# canSlaveV01a0.net
KiCad netlist of a schematic drawn in EAGLE
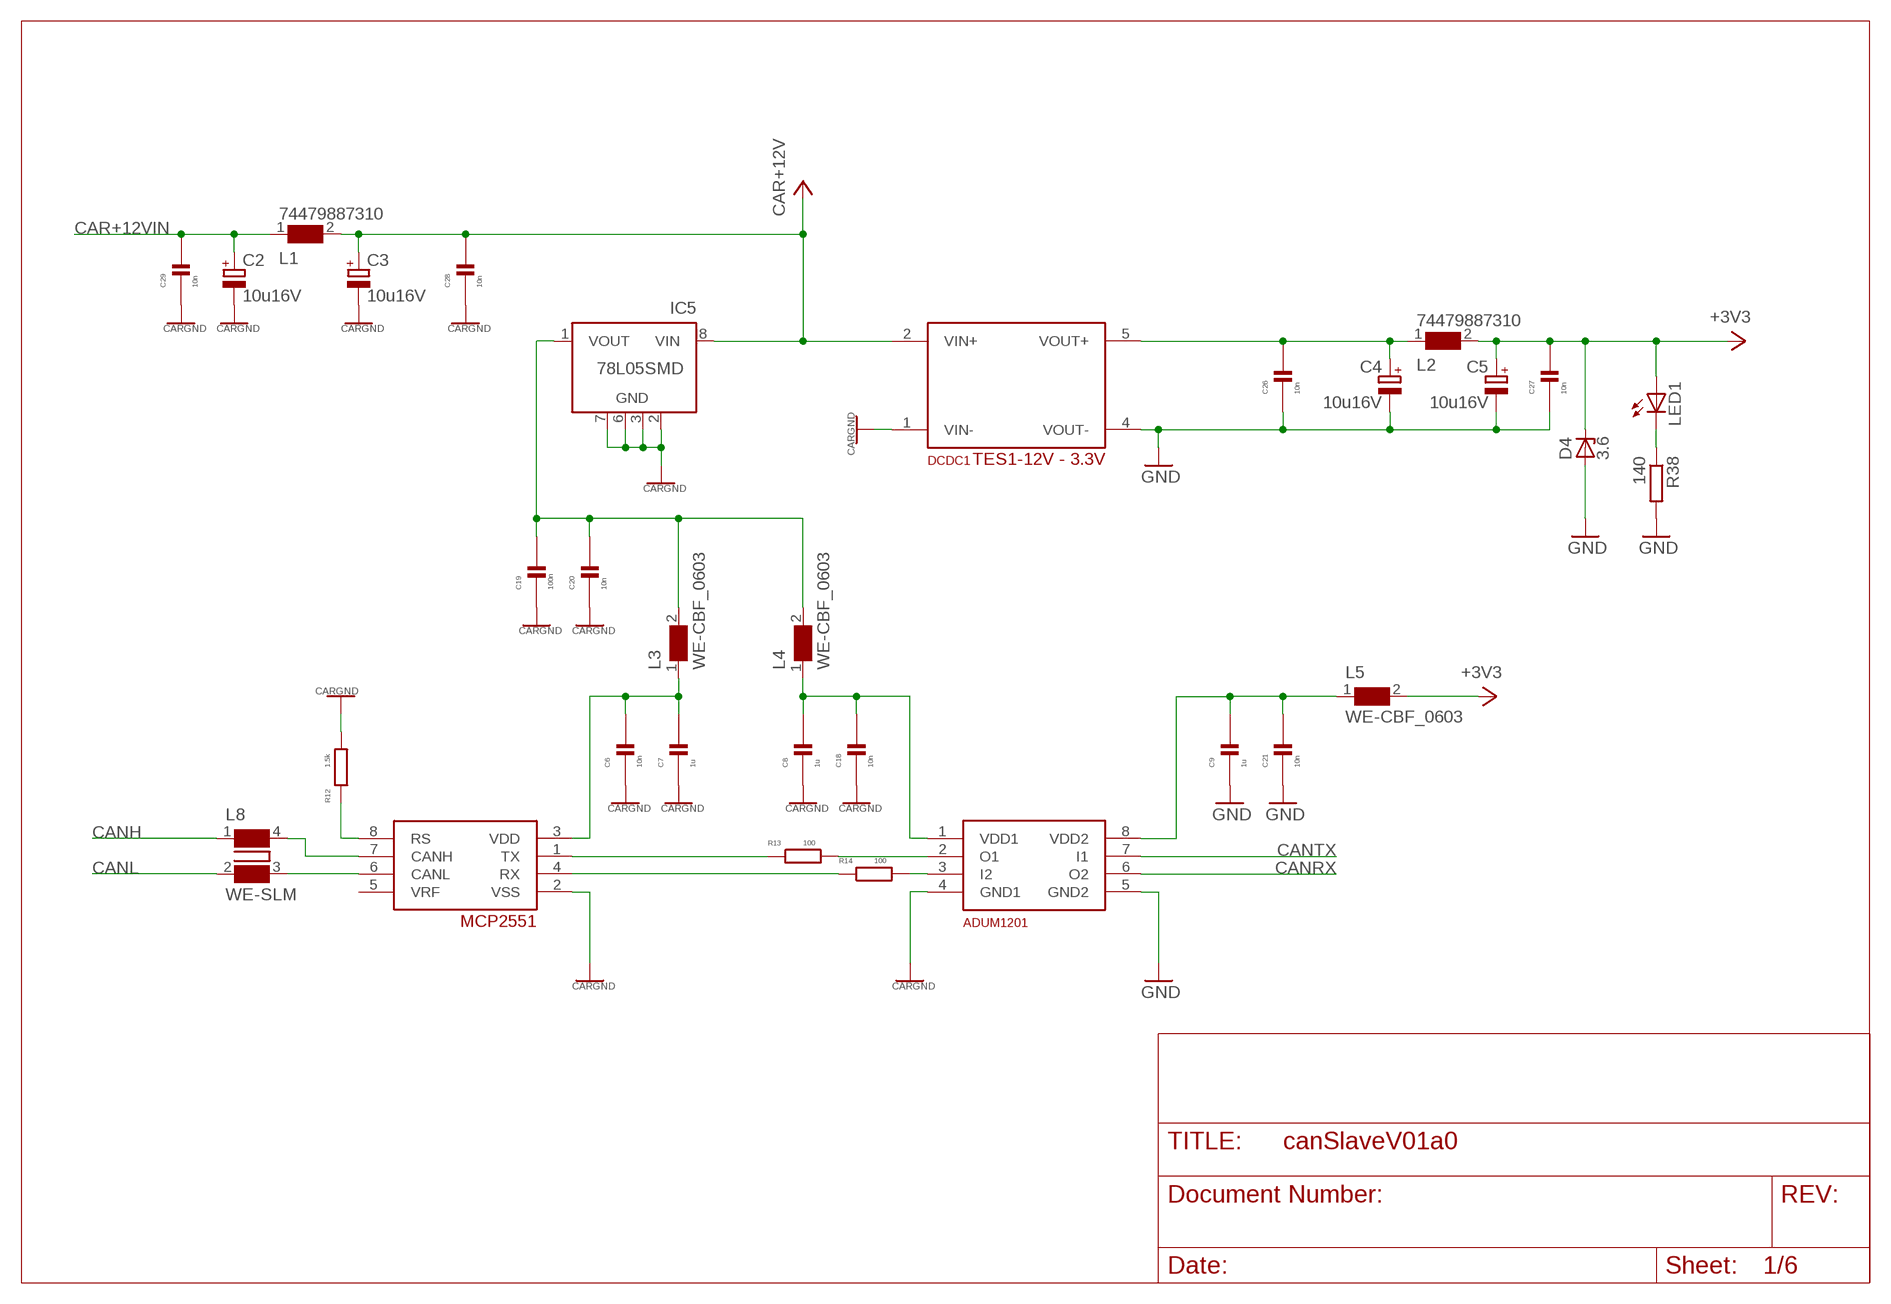
[diagram p0: schematic, sheet 1]
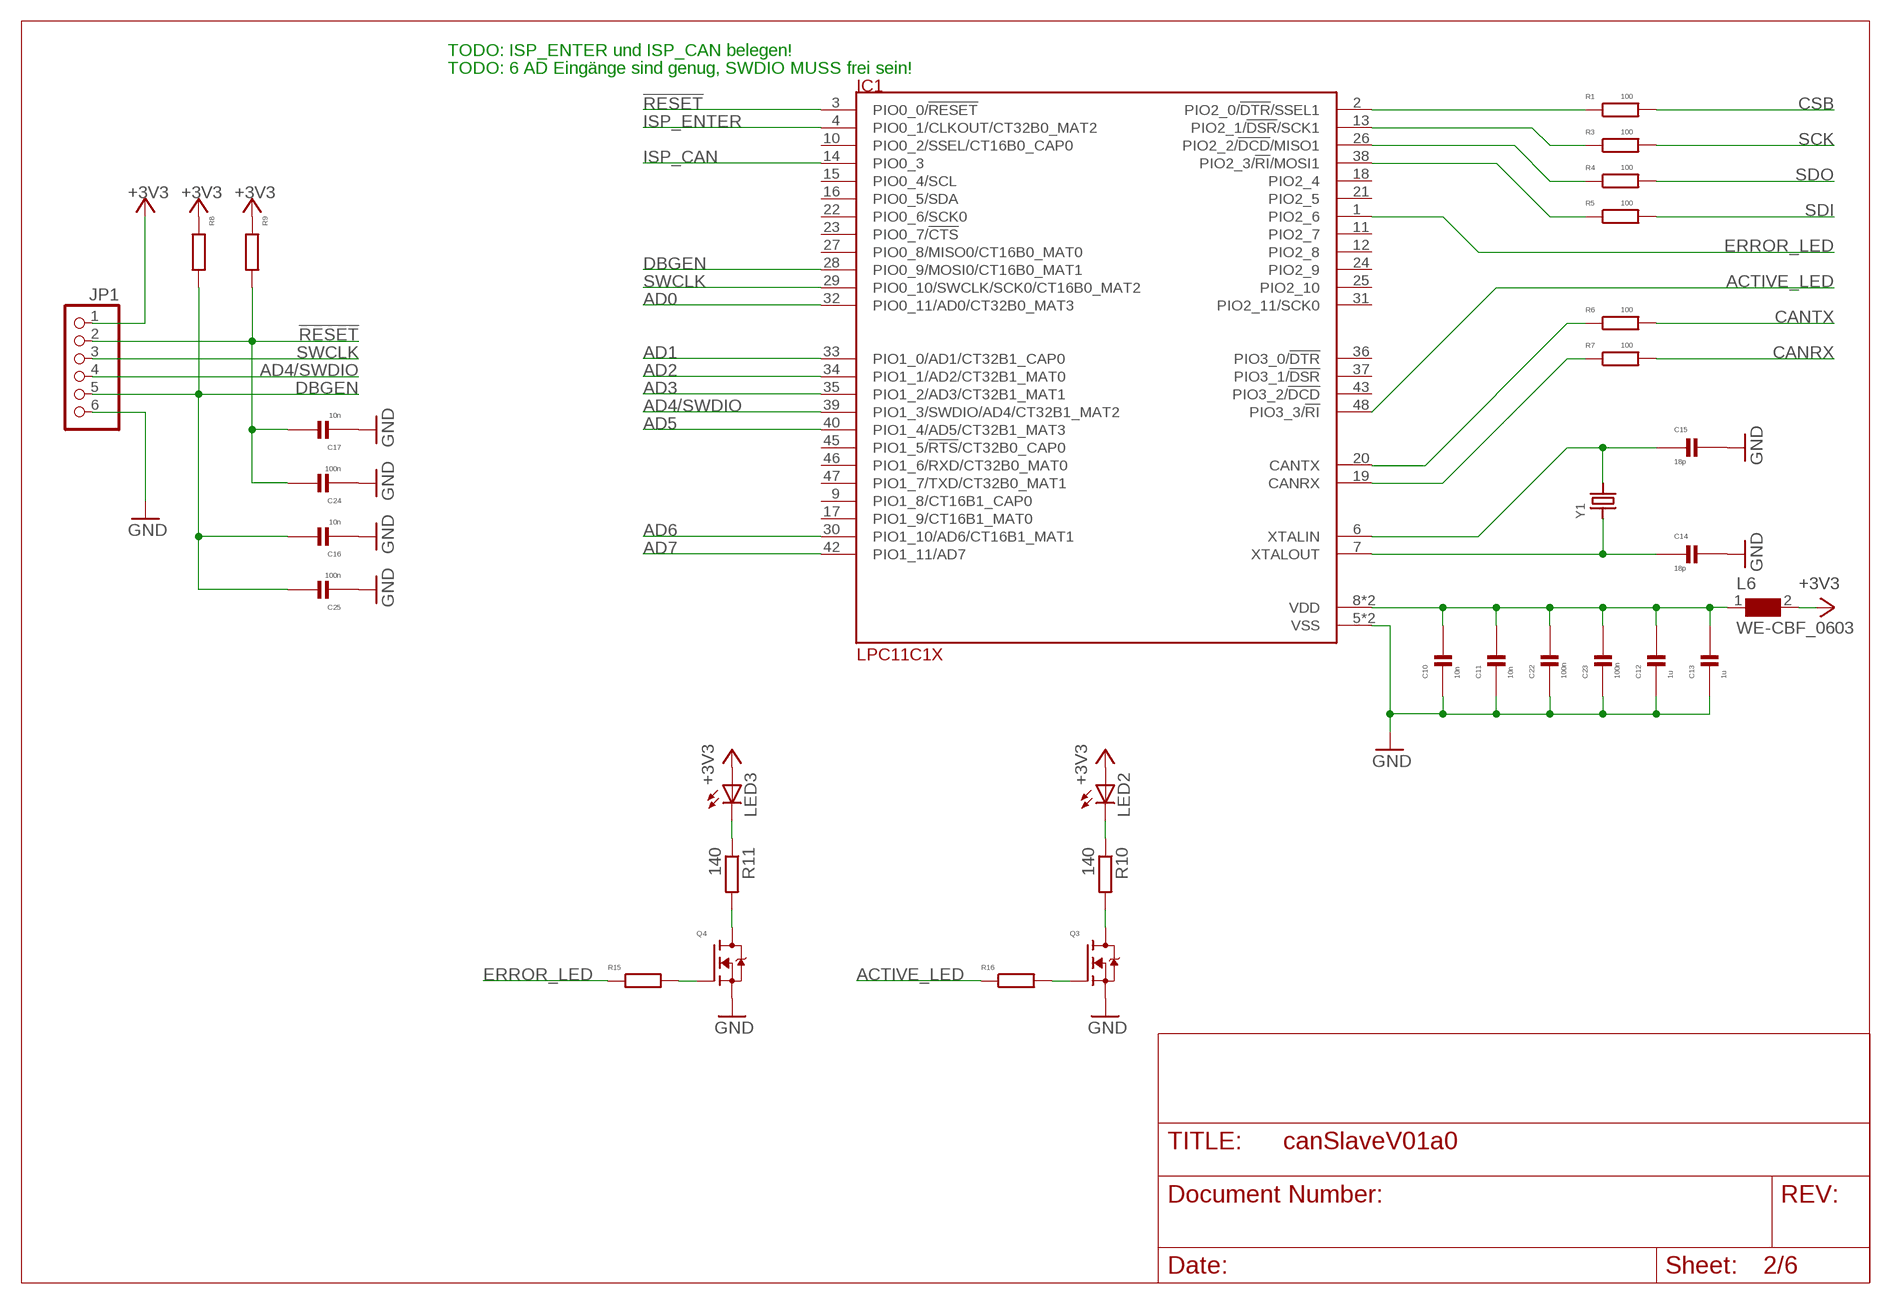
[diagram p1: schematic, sheet 2]
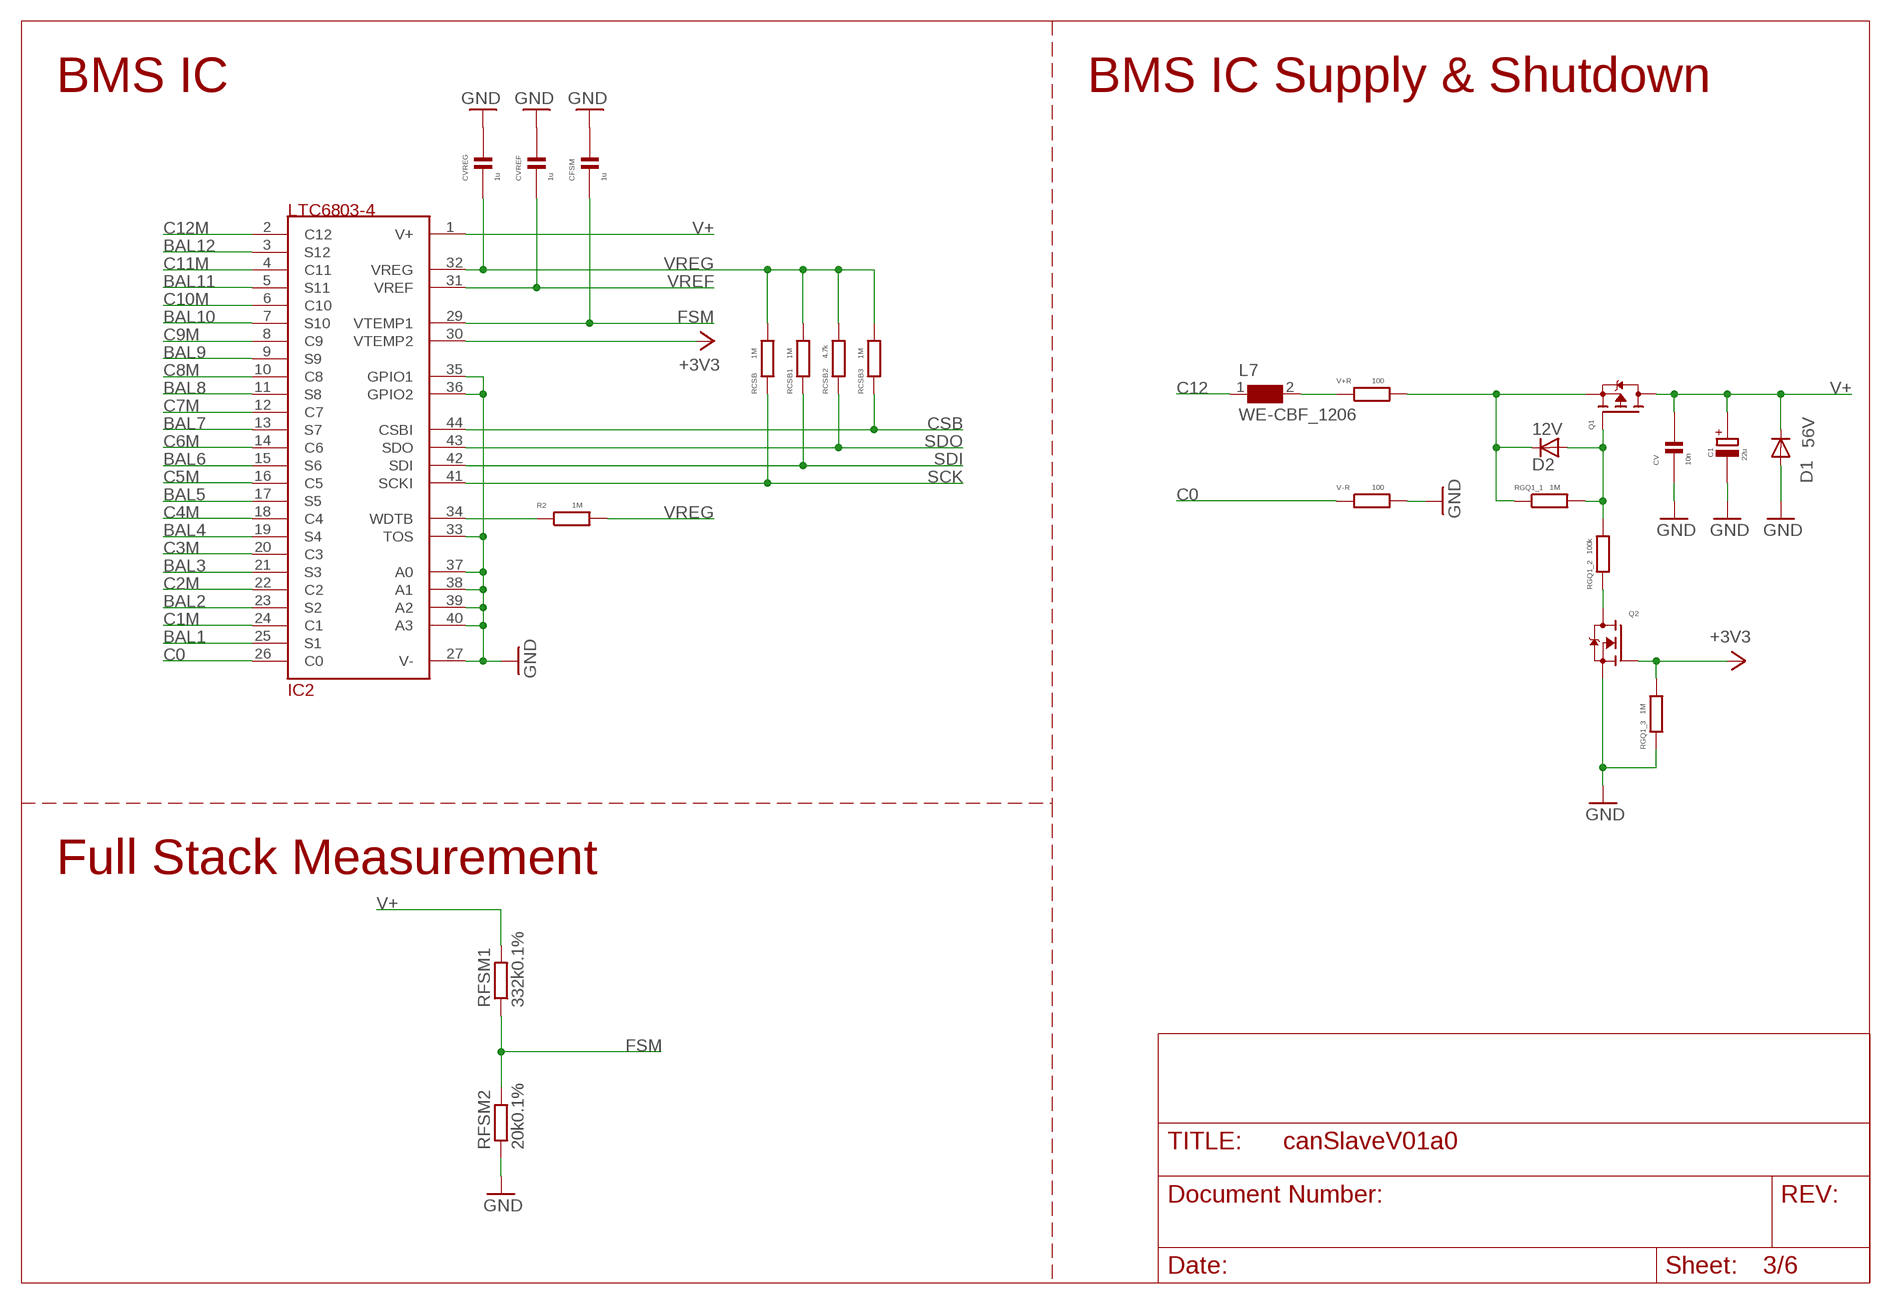
[diagram p2: schematic, sheet 3]
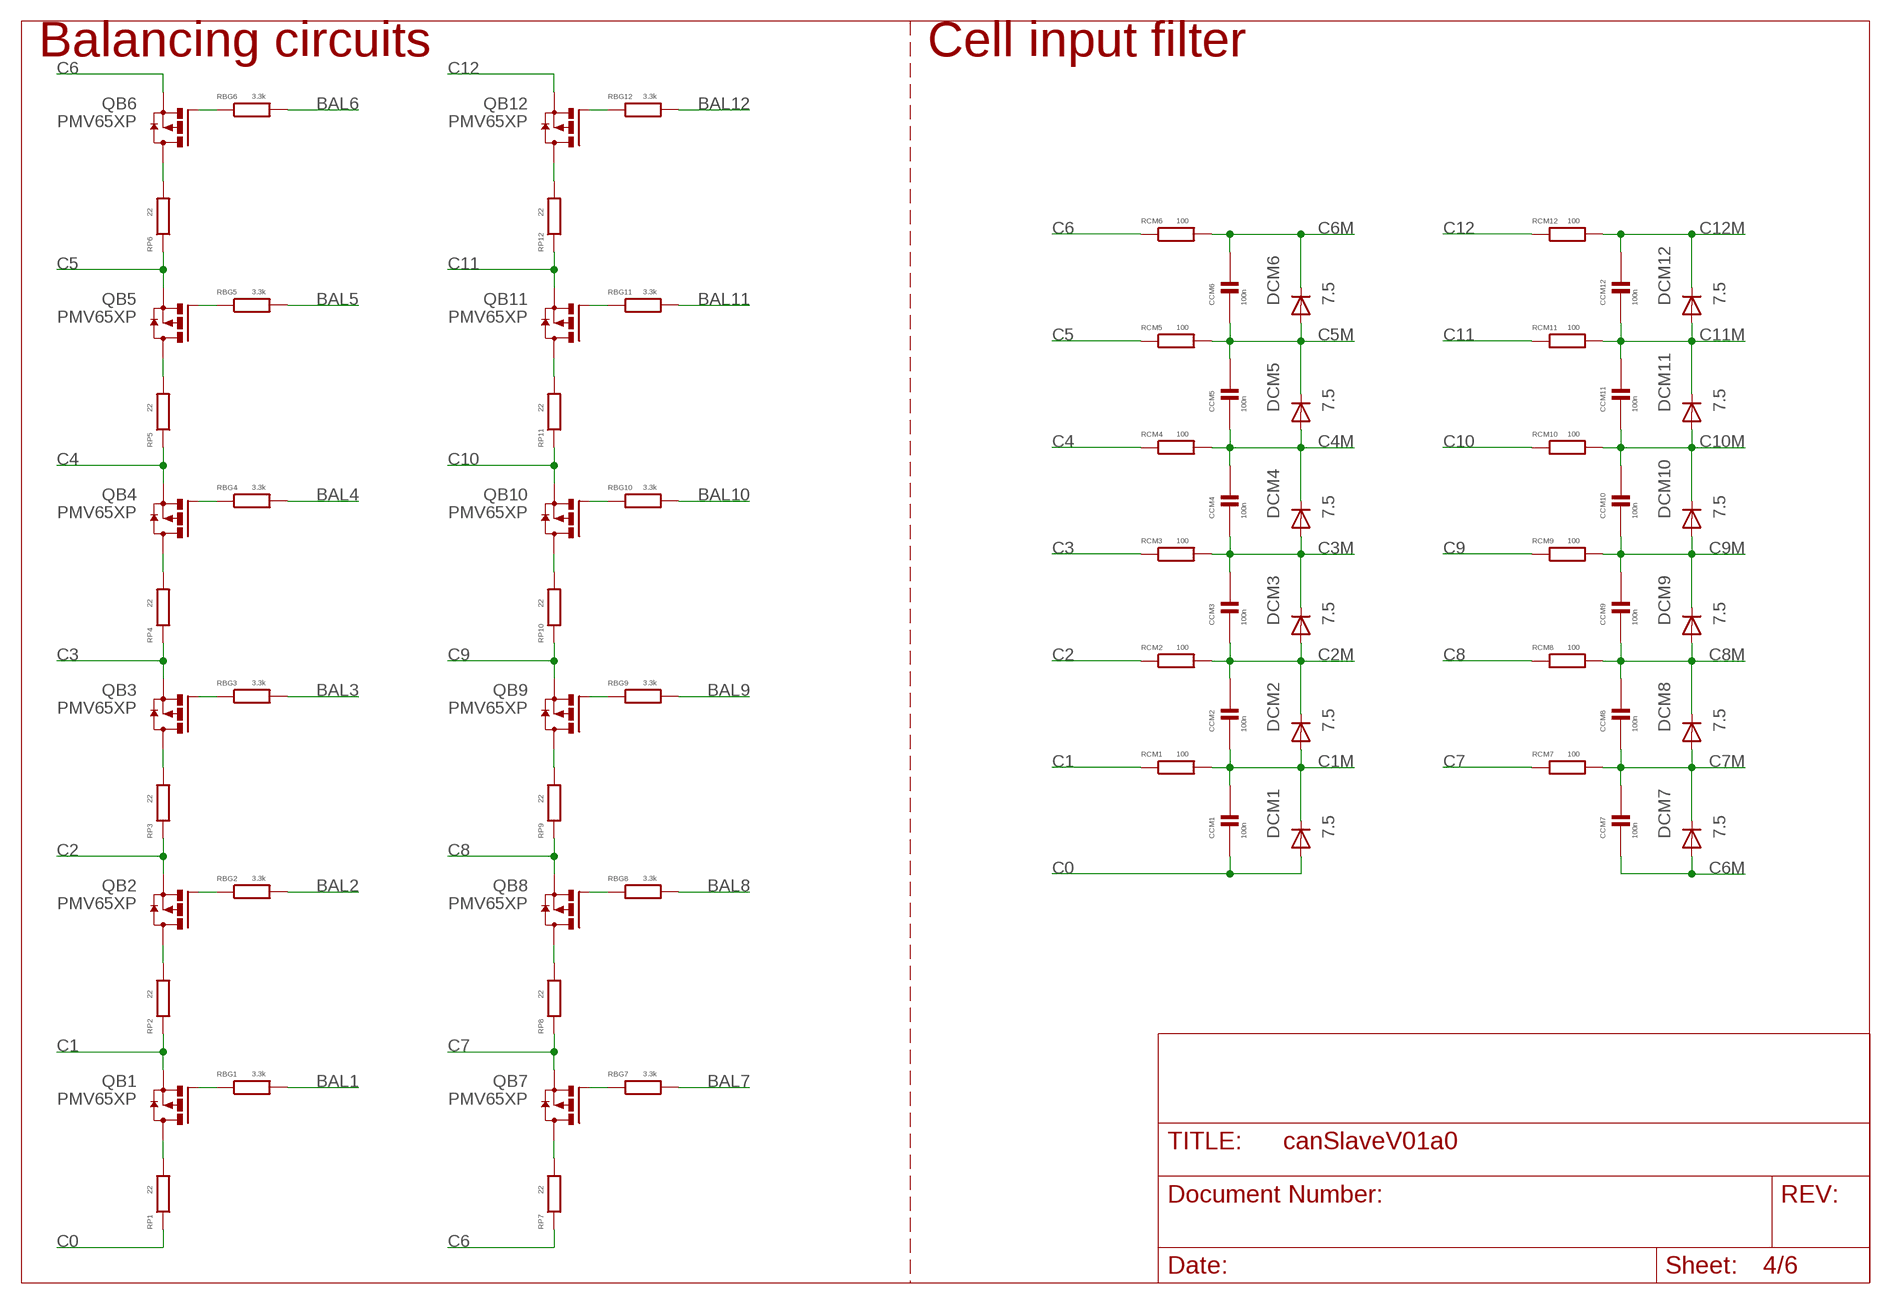
[diagram p3: schematic, sheet 4]
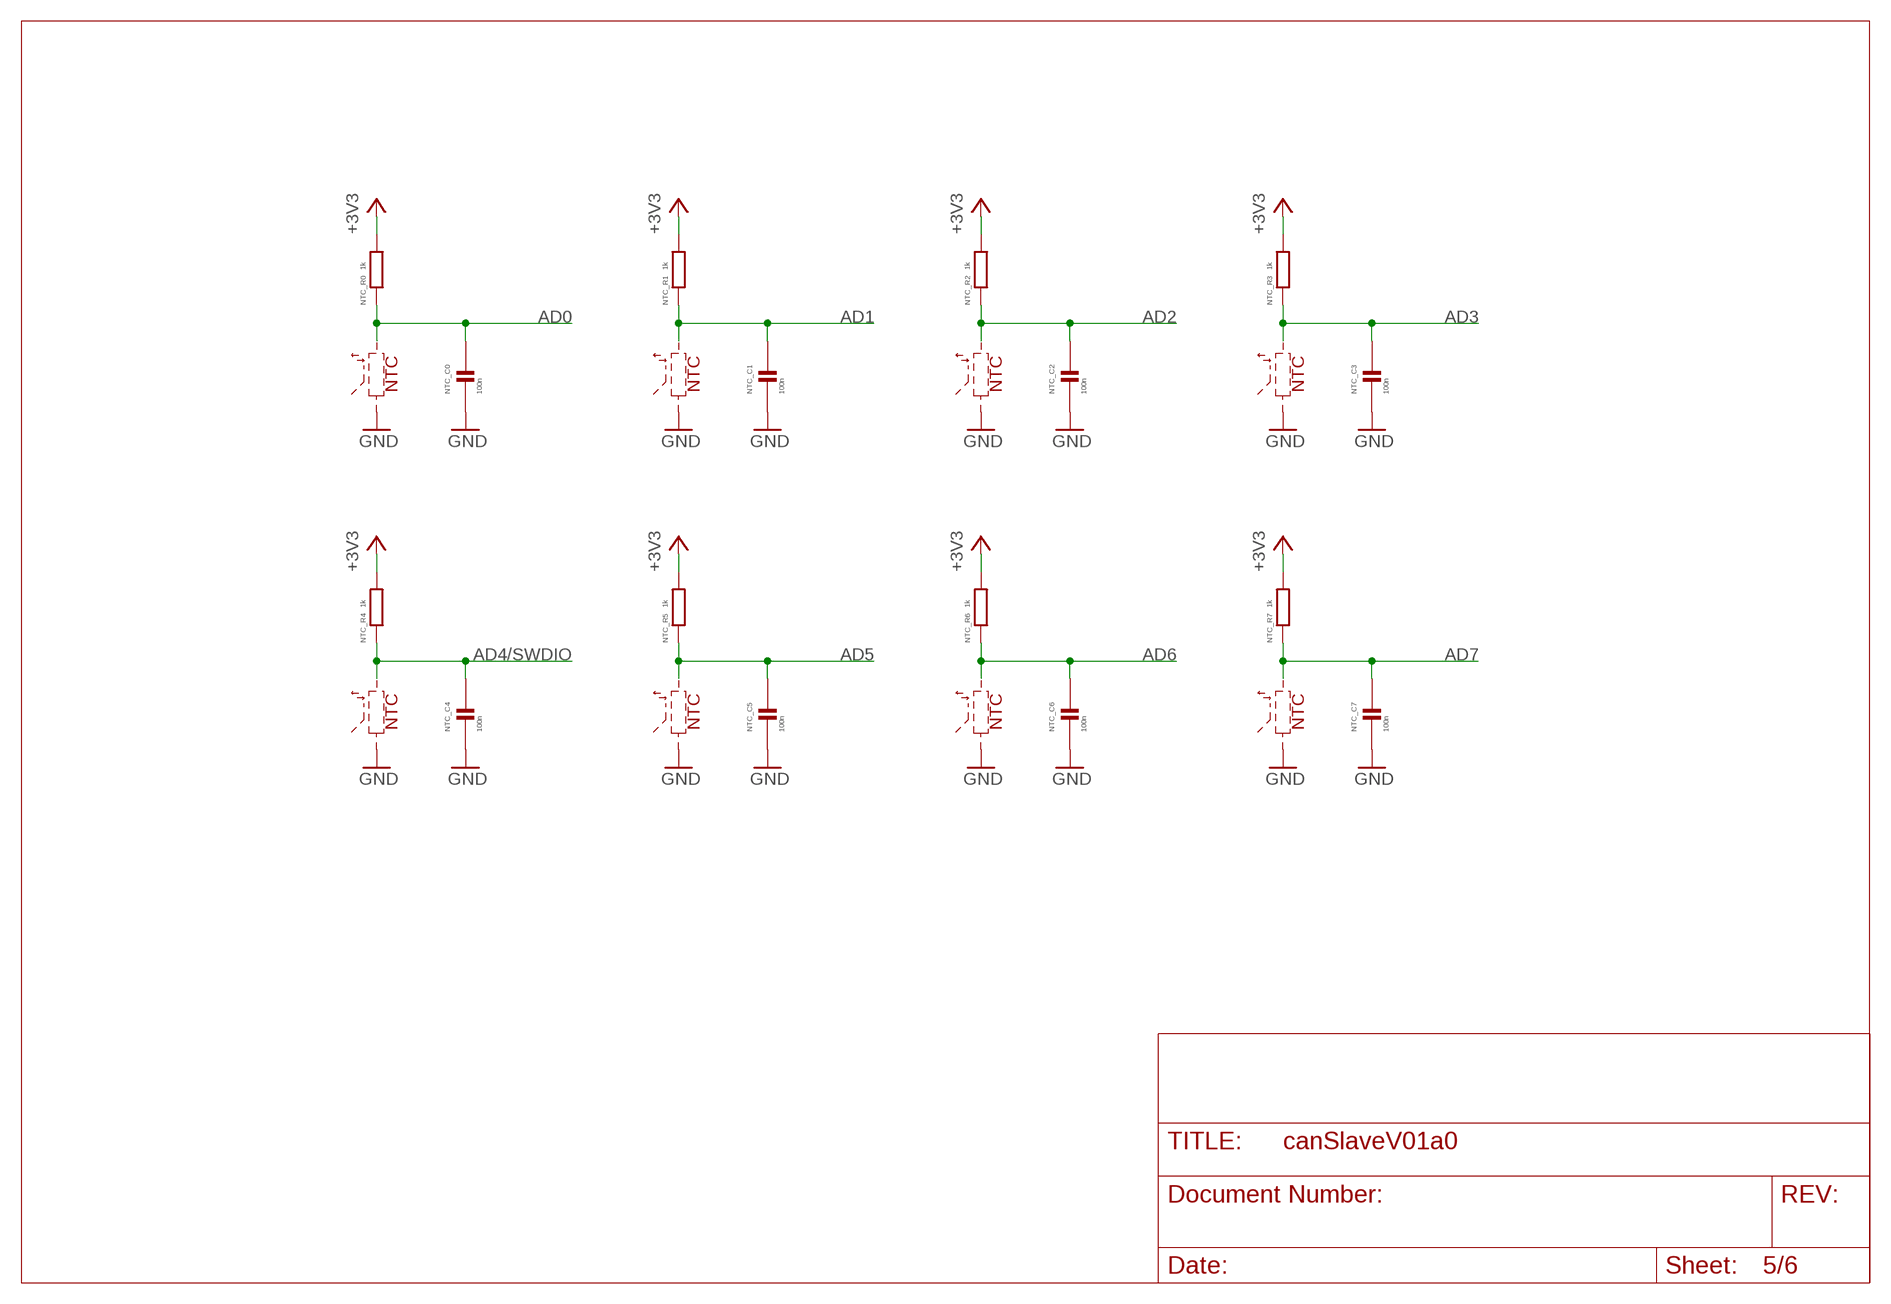
[diagram p4: schematic, sheet 5]
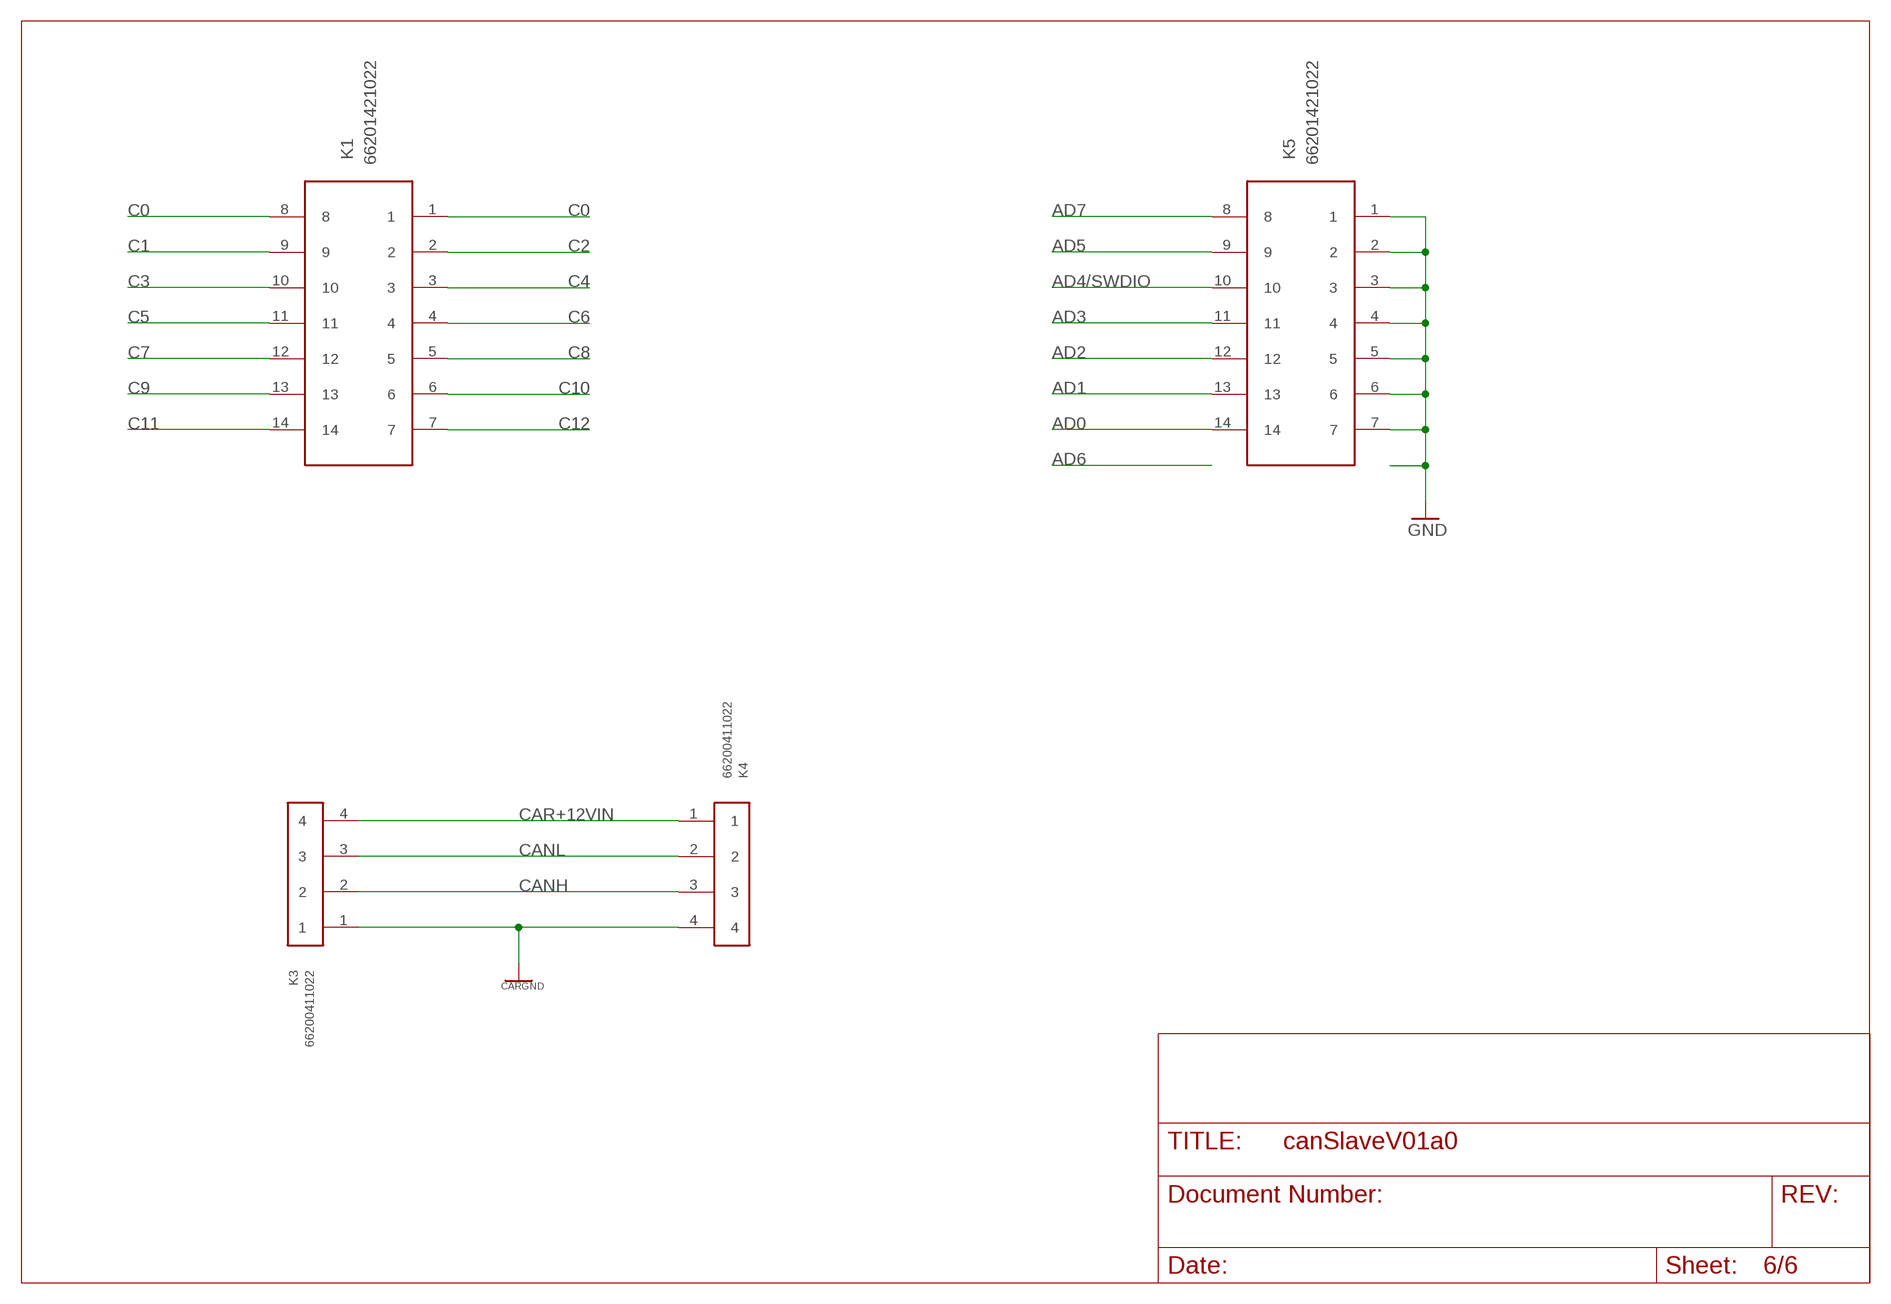
[diagram p5: schematic, sheet 6]

(export (version "E")
  (design (tool "Eeschema 10.0.6"))
  (components
    (comp (ref "NTC_C0")
      (value "100n")
      (footprint "eagle-import:C0603")
      (libsource (lib "eagle-import") (part "C0603"))
    )
    (comp (ref "NTC_C1")
      (value "100n")
      (footprint "eagle-import:C0603")
      (libsource (lib "eagle-import") (part "C0603"))
    )
    (comp (ref "NTC_C2")
      (value "100n")
      (footprint "eagle-import:C0603")
      (libsource (lib "eagle-import") (part "C0603"))
    )
    (comp (ref "NTC_C3")
      (value "100n")
      (footprint "eagle-import:C0603")
      (libsource (lib "eagle-import") (part "C0603"))
    )
    (comp (ref "NTC_C4")
      (value "100n")
      (footprint "eagle-import:C0603")
      (libsource (lib "eagle-import") (part "C0603"))
    )
    (comp (ref "NTC_C5")
      (value "100n")
      (footprint "eagle-import:C0603")
      (libsource (lib "eagle-import") (part "C0603"))
    )
    (comp (ref "NTC_C6")
      (value "100n")
      (footprint "eagle-import:C0603")
      (libsource (lib "eagle-import") (part "C0603"))
    )
    (comp (ref "NTC_C7")
      (value "100n")
      (footprint "eagle-import:C0603")
      (libsource (lib "eagle-import") (part "C0603"))
    )
    (comp (ref "NTC_R0")
      (value "1k")
      (footprint "eagle-import:R0603")
      (libsource (lib "eagle-import") (part "R0603"))
    )
    (comp (ref "NTC_R1")
      (value "1k")
      (footprint "eagle-import:R0603")
      (libsource (lib "eagle-import") (part "R0603"))
    )
    (comp (ref "NTC_R2")
      (value "1k")
      (footprint "eagle-import:R0603")
      (libsource (lib "eagle-import") (part "R0603"))
    )
    (comp (ref "NTC_R3")
      (value "1k")
      (footprint "eagle-import:R0603")
      (libsource (lib "eagle-import") (part "R0603"))
    )
    (comp (ref "NTC_R4")
      (value "1k")
      (footprint "eagle-import:R0603")
      (libsource (lib "eagle-import") (part "R0603"))
    )
    (comp (ref "NTC_R5")
      (value "1k")
      (footprint "eagle-import:R0603")
      (libsource (lib "eagle-import") (part "R0603"))
    )
    (comp (ref "NTC_R6")
      (value "1k")
      (footprint "eagle-import:R0603")
      (libsource (lib "eagle-import") (part "R0603"))
    )
    (comp (ref "NTC_R7")
      (value "1k")
      (footprint "eagle-import:R0603")
      (libsource (lib "eagle-import") (part "R0603"))
    )
    (comp (ref "C2")
      (value "10u16V")
      (footprint "eagle-import:PANASONIC_B")
      (libsource (lib "eagle-import") (part "CPOL-EUB"))
    )
    (comp (ref "C3")
      (value "10u16V")
      (footprint "eagle-import:PANASONIC_B")
      (libsource (lib "eagle-import") (part "CPOL-EUB"))
    )
    (comp (ref "C4")
      (value "10u16V")
      (footprint "eagle-import:PANASONIC_B")
      (libsource (lib "eagle-import") (part "CPOL-EUB"))
    )
    (comp (ref "C5")
      (value "10u16V")
      (footprint "eagle-import:PANASONIC_B")
      (libsource (lib "eagle-import") (part "CPOL-EUB"))
    )
    (comp (ref "C6")
      (value "10n")
      (footprint "eagle-import:C0603")
      (libsource (lib "eagle-import") (part "C0603"))
    )
    (comp (ref "C7")
      (value "1u")
      (footprint "eagle-import:C0603")
      (libsource (lib "eagle-import") (part "C0603"))
    )
    (comp (ref "C8")
      (value "1u")
      (footprint "eagle-import:C0603")
      (libsource (lib "eagle-import") (part "C0603"))
    )
    (comp (ref "C9")
      (value "1u")
      (footprint "eagle-import:C0603")
      (libsource (lib "eagle-import") (part "C0603"))
    )
    (comp (ref "C18")
      (value "10n")
      (footprint "eagle-import:C0603")
      (libsource (lib "eagle-import") (part "C0603"))
    )
    (comp (ref "C19")
      (value "100n")
      (footprint "eagle-import:C0603")
      (libsource (lib "eagle-import") (part "C0603"))
    )
    (comp (ref "C20")
      (value "10n")
      (footprint "eagle-import:C0603")
      (libsource (lib "eagle-import") (part "C0603"))
    )
    (comp (ref "C21")
      (value "10n")
      (footprint "eagle-import:C0603")
      (libsource (lib "eagle-import") (part "C0603"))
    )
    (comp (ref "C26")
      (value "10n")
      (footprint "eagle-import:C0603")
      (libsource (lib "eagle-import") (part "C0603"))
    )
    (comp (ref "C27")
      (value "10n")
      (footprint "eagle-import:C0603")
      (libsource (lib "eagle-import") (part "C0603"))
    )
    (comp (ref "C28")
      (value "10n")
      (footprint "eagle-import:C0603")
      (libsource (lib "eagle-import") (part "C0603"))
    )
    (comp (ref "C29")
      (value "10n")
      (footprint "eagle-import:C0603")
      (libsource (lib "eagle-import") (part "C0603"))
    )
    (comp (ref "D4")
      (value "3.6")
      (footprint "eagle-import:SOD323-W")
      (libsource (lib "eagle-import") (part "ZENER-DIODESOD323"))
    )
    (comp (ref "DCDC1")
      (value "TES1-12V - 3.3V")
      (footprint "eagle-import:ISF")
      (libsource (lib "eagle-import") (part "ISFXXXXA"))
    )
    (comp (ref "IC3")
      (value "ADUM1201")
      (footprint "eagle-import:SO-8")
      (libsource (lib "eagle-import") (part "ADUM1201"))
    )
    (comp (ref "IC4")
      (value "MCP2551")
      (footprint "eagle-import:SO-8")
      (libsource (lib "eagle-import") (part "MCP2551"))
    )
    (comp (ref "IC5")
      (value "78L05SMD")
      (footprint "eagle-import:SO08")
      (libsource (lib "eagle-import") (part "78LSMD05"))
    )
    (comp (ref "L1")
      (value "74479887310")
      (footprint "eagle-import:WE-PMI_1008")
      (libsource (lib "eagle-import") (part "WE-PMI_1008"))
    )
    (comp (ref "L2")
      (value "74479887310")
      (footprint "eagle-import:WE-PMI_1008")
      (libsource (lib "eagle-import") (part "WE-PMI_1008"))
    )
    (comp (ref "L3")
      (value "WE-CBF_0603")
      (footprint "eagle-import:0603")
      (libsource (lib "eagle-import") (part "WE-CBF_0603"))
    )
    (comp (ref "L4")
      (value "WE-CBF_0603")
      (footprint "eagle-import:0603")
      (libsource (lib "eagle-import") (part "WE-CBF_0603"))
    )
    (comp (ref "L5")
      (value "WE-CBF_0603")
      (footprint "eagle-import:0603")
      (libsource (lib "eagle-import") (part "WE-CBF_0603"))
    )
    (comp (ref "L8")
      (value "WE-SLM")
      (footprint "eagle-import:WE-SLM")
      (libsource (lib "eagle-import") (part "WE-SLM"))
    )
    (comp (ref "LED1")
      (value "LEDCHIPLED_1206")
      (footprint "eagle-import:CHIPLED_1206")
      (libsource (lib "eagle-import") (part "LEDCHIPLED_1206"))
    )
    (comp (ref "R12")
      (value "1.5k")
      (footprint "eagle-import:R0603")
      (libsource (lib "eagle-import") (part "R0603"))
    )
    (comp (ref "R13")
      (value "100")
      (footprint "eagle-import:R0603")
      (libsource (lib "eagle-import") (part "R0603"))
    )
    (comp (ref "R14")
      (value "100")
      (footprint "eagle-import:R0603")
      (libsource (lib "eagle-import") (part "R0603"))
    )
    (comp (ref "R38")
      (value "140")
      (footprint "eagle-import:R1206")
      (libsource (lib "eagle-import") (part "R-EU_R1206"))
    )
    (comp (ref "K1")
      (value "66201421022")
      (footprint "eagle-import:66201421022")
      (libsource (lib "eagle-import") (part "66201421022"))
    )
    (comp (ref "K3")
      (value "66200411022")
      (footprint "eagle-import:66200411022")
      (libsource (lib "eagle-import") (part "66200411022"))
    )
    (comp (ref "K4")
      (value "66200411022")
      (footprint "eagle-import:66200411022")
      (libsource (lib "eagle-import") (part "66200411022"))
    )
    (comp (ref "K5")
      (value "66201421022")
      (footprint "eagle-import:66201421022")
      (libsource (lib "eagle-import") (part "66201421022"))
    )
    (comp (ref "CCM1")
      (value "100n")
      (footprint "eagle-import:C0603")
      (libsource (lib "eagle-import") (part "C0603"))
    )
    (comp (ref "CCM2")
      (value "100n")
      (footprint "eagle-import:C0603")
      (libsource (lib "eagle-import") (part "C0603"))
    )
    (comp (ref "CCM3")
      (value "100n")
      (footprint "eagle-import:C0603")
      (libsource (lib "eagle-import") (part "C0603"))
    )
    (comp (ref "CCM4")
      (value "100n")
      (footprint "eagle-import:C0603")
      (libsource (lib "eagle-import") (part "C0603"))
    )
    (comp (ref "CCM5")
      (value "100n")
      (footprint "eagle-import:C0603")
      (libsource (lib "eagle-import") (part "C0603"))
    )
    (comp (ref "CCM6")
      (value "100n")
      (footprint "eagle-import:C0603")
      (libsource (lib "eagle-import") (part "C0603"))
    )
    (comp (ref "CCM7")
      (value "100n")
      (footprint "eagle-import:C0603")
      (libsource (lib "eagle-import") (part "C0603"))
    )
    (comp (ref "CCM8")
      (value "100n")
      (footprint "eagle-import:C0603")
      (libsource (lib "eagle-import") (part "C0603"))
    )
    (comp (ref "CCM9")
      (value "100n")
      (footprint "eagle-import:C0603")
      (libsource (lib "eagle-import") (part "C0603"))
    )
    (comp (ref "CCM10")
      (value "100n")
      (footprint "eagle-import:C0603")
      (libsource (lib "eagle-import") (part "C0603"))
    )
    (comp (ref "CCM11")
      (value "100n")
      (footprint "eagle-import:C0603")
      (libsource (lib "eagle-import") (part "C0603"))
    )
    (comp (ref "CCM12")
      (value "100n")
      (footprint "eagle-import:C0603")
      (libsource (lib "eagle-import") (part "C0603"))
    )
    (comp (ref "DCM1")
      (value "7.5")
      (footprint "eagle-import:SOD323-R")
      (libsource (lib "eagle-import") (part "DIODE-SOD323-R"))
    )
    (comp (ref "DCM2")
      (value "7.5")
      (footprint "eagle-import:SOD323-R")
      (libsource (lib "eagle-import") (part "DIODE-SOD323-R"))
    )
    (comp (ref "DCM3")
      (value "7.5")
      (footprint "eagle-import:SOD323-R")
      (libsource (lib "eagle-import") (part "DIODE-SOD323-R"))
    )
    (comp (ref "DCM4")
      (value "7.5")
      (footprint "eagle-import:SOD323-R")
      (libsource (lib "eagle-import") (part "DIODE-SOD323-R"))
    )
    (comp (ref "DCM5")
      (value "7.5")
      (footprint "eagle-import:SOD323-R")
      (libsource (lib "eagle-import") (part "DIODE-SOD323-R"))
    )
    (comp (ref "DCM6")
      (value "7.5")
      (footprint "eagle-import:SOD323-R")
      (libsource (lib "eagle-import") (part "DIODE-SOD323-R"))
    )
    (comp (ref "DCM7")
      (value "7.5")
      (footprint "eagle-import:SOD323-R")
      (libsource (lib "eagle-import") (part "DIODE-SOD323-R"))
    )
    (comp (ref "DCM8")
      (value "7.5")
      (footprint "eagle-import:SOD323-R")
      (libsource (lib "eagle-import") (part "DIODE-SOD323-R"))
    )
    (comp (ref "DCM9")
      (value "7.5")
      (footprint "eagle-import:SOD323-R")
      (libsource (lib "eagle-import") (part "DIODE-SOD323-R"))
    )
    (comp (ref "DCM10")
      (value "7.5")
      (footprint "eagle-import:SOD323-R")
      (libsource (lib "eagle-import") (part "DIODE-SOD323-R"))
    )
    (comp (ref "DCM11")
      (value "7.5")
      (footprint "eagle-import:SOD323-R")
      (libsource (lib "eagle-import") (part "DIODE-SOD323-R"))
    )
    (comp (ref "DCM12")
      (value "7.5")
      (footprint "eagle-import:SOD323-R")
      (libsource (lib "eagle-import") (part "DIODE-SOD323-R"))
    )
    (comp (ref "QB1")
      (value "PMV65XP")
      (footprint "eagle-import:SUPER-SOT3")
      (libsource (lib "eagle-import") (part "FDN360P"))
    )
    (comp (ref "QB2")
      (value "PMV65XP")
      (footprint "eagle-import:SUPER-SOT3")
      (libsource (lib "eagle-import") (part "FDN360P"))
    )
    (comp (ref "QB3")
      (value "PMV65XP")
      (footprint "eagle-import:SUPER-SOT3")
      (libsource (lib "eagle-import") (part "FDN360P"))
    )
    (comp (ref "QB4")
      (value "PMV65XP")
      (footprint "eagle-import:SUPER-SOT3")
      (libsource (lib "eagle-import") (part "FDN360P"))
    )
    (comp (ref "QB5")
      (value "PMV65XP")
      (footprint "eagle-import:SUPER-SOT3")
      (libsource (lib "eagle-import") (part "FDN360P"))
    )
    (comp (ref "QB6")
      (value "PMV65XP")
      (footprint "eagle-import:SUPER-SOT3")
      (libsource (lib "eagle-import") (part "FDN360P"))
    )
    (comp (ref "QB7")
      (value "PMV65XP")
      (footprint "eagle-import:SUPER-SOT3")
      (libsource (lib "eagle-import") (part "FDN360P"))
    )
    (comp (ref "QB8")
      (value "PMV65XP")
      (footprint "eagle-import:SUPER-SOT3")
      (libsource (lib "eagle-import") (part "FDN360P"))
    )
    (comp (ref "QB9")
      (value "PMV65XP")
      (footprint "eagle-import:SUPER-SOT3")
      (libsource (lib "eagle-import") (part "FDN360P"))
    )
    (comp (ref "QB10")
      (value "PMV65XP")
      (footprint "eagle-import:SUPER-SOT3")
      (libsource (lib "eagle-import") (part "FDN360P"))
    )
    (comp (ref "QB11")
      (value "PMV65XP")
      (footprint "eagle-import:SUPER-SOT3")
      (libsource (lib "eagle-import") (part "FDN360P"))
    )
    (comp (ref "QB12")
      (value "PMV65XP")
      (footprint "eagle-import:SUPER-SOT3")
      (libsource (lib "eagle-import") (part "FDN360P"))
    )
    (comp (ref "RBG1")
      (value "3.3k")
      (footprint "eagle-import:R0603")
      (libsource (lib "eagle-import") (part "R0603"))
    )
    (comp (ref "RBG2")
      (value "3.3k")
      (footprint "eagle-import:R0603")
      (libsource (lib "eagle-import") (part "R0603"))
    )
    (comp (ref "RBG3")
      (value "3.3k")
      (footprint "eagle-import:R0603")
      (libsource (lib "eagle-import") (part "R0603"))
    )
    (comp (ref "RBG4")
      (value "3.3k")
      (footprint "eagle-import:R0603")
      (libsource (lib "eagle-import") (part "R0603"))
    )
    (comp (ref "RBG5")
      (value "3.3k")
      (footprint "eagle-import:R0603")
      (libsource (lib "eagle-import") (part "R0603"))
    )
    (comp (ref "RBG6")
      (value "3.3k")
      (footprint "eagle-import:R0603")
      (libsource (lib "eagle-import") (part "R0603"))
    )
    (comp (ref "RBG7")
      (value "3.3k")
      (footprint "eagle-import:R0603")
      (libsource (lib "eagle-import") (part "R0603"))
    )
    (comp (ref "RBG8")
      (value "3.3k")
      (footprint "eagle-import:R0603")
      (libsource (lib "eagle-import") (part "R0603"))
    )
    (comp (ref "RBG9")
      (value "3.3k")
      (footprint "eagle-import:R0603")
      (libsource (lib "eagle-import") (part "R0603"))
    )
    (comp (ref "RBG10")
      (value "3.3k")
      (footprint "eagle-import:R0603")
      (libsource (lib "eagle-import") (part "R0603"))
    )
    (comp (ref "RBG11")
      (value "3.3k")
      (footprint "eagle-import:R0603")
      (libsource (lib "eagle-import") (part "R0603"))
    )
    (comp (ref "RBG12")
      (value "3.3k")
      (footprint "eagle-import:R0603")
      (libsource (lib "eagle-import") (part "R0603"))
    )
    (comp (ref "RCM1")
      (value "100")
      (footprint "eagle-import:R0603")
      (libsource (lib "eagle-import") (part "R0603"))
    )
    (comp (ref "RCM2")
      (value "100")
      (footprint "eagle-import:R0603")
      (libsource (lib "eagle-import") (part "R0603"))
    )
    (comp (ref "RCM3")
      (value "100")
      (footprint "eagle-import:R0603")
      (libsource (lib "eagle-import") (part "R0603"))
    )
    (comp (ref "RCM4")
      (value "100")
      (footprint "eagle-import:R0603")
      (libsource (lib "eagle-import") (part "R0603"))
    )
    (comp (ref "RCM5")
      (value "100")
      (footprint "eagle-import:R0603")
      (libsource (lib "eagle-import") (part "R0603"))
    )
    (comp (ref "RCM6")
      (value "100")
      (footprint "eagle-import:R0603")
      (libsource (lib "eagle-import") (part "R0603"))
    )
    (comp (ref "RCM7")
      (value "100")
      (footprint "eagle-import:R0603")
      (libsource (lib "eagle-import") (part "R0603"))
    )
    (comp (ref "RCM8")
      (value "100")
      (footprint "eagle-import:R0603")
      (libsource (lib "eagle-import") (part "R0603"))
    )
    (comp (ref "RCM9")
      (value "100")
      (footprint "eagle-import:R0603")
      (libsource (lib "eagle-import") (part "R0603"))
    )
    (comp (ref "RCM10")
      (value "100")
      (footprint "eagle-import:R0603")
      (libsource (lib "eagle-import") (part "R0603"))
    )
    (comp (ref "RCM11")
      (value "100")
      (footprint "eagle-import:R0603")
      (libsource (lib "eagle-import") (part "R0603"))
    )
    (comp (ref "RCM12")
      (value "100")
      (footprint "eagle-import:R0603")
      (libsource (lib "eagle-import") (part "R0603"))
    )
    (comp (ref "RP1")
      (value "22")
      (footprint "eagle-import:R2512")
      (libsource (lib "eagle-import") (part "R2512"))
    )
    (comp (ref "RP2")
      (value "22")
      (footprint "eagle-import:R2512")
      (libsource (lib "eagle-import") (part "R2512"))
    )
    (comp (ref "RP3")
      (value "22")
      (footprint "eagle-import:R2512")
      (libsource (lib "eagle-import") (part "R2512"))
    )
    (comp (ref "RP4")
      (value "22")
      (footprint "eagle-import:R2512")
      (libsource (lib "eagle-import") (part "R2512"))
    )
    (comp (ref "RP5")
      (value "22")
      (footprint "eagle-import:R2512")
      (libsource (lib "eagle-import") (part "R2512"))
    )
    (comp (ref "RP6")
      (value "22")
      (footprint "eagle-import:R2512")
      (libsource (lib "eagle-import") (part "R2512"))
    )
    (comp (ref "RP7")
      (value "22")
      (footprint "eagle-import:R2512")
      (libsource (lib "eagle-import") (part "R2512"))
    )
    (comp (ref "RP8")
      (value "22")
      (footprint "eagle-import:R2512")
      (libsource (lib "eagle-import") (part "R2512"))
    )
    (comp (ref "RP9")
      (value "22")
      (footprint "eagle-import:R2512")
      (libsource (lib "eagle-import") (part "R2512"))
    )
    (comp (ref "RP10")
      (value "22")
      (footprint "eagle-import:R2512")
      (libsource (lib "eagle-import") (part "R2512"))
    )
    (comp (ref "RP11")
      (value "22")
      (footprint "eagle-import:R2512")
      (libsource (lib "eagle-import") (part "R2512"))
    )
    (comp (ref "RP12")
      (value "22")
      (footprint "eagle-import:R2512")
      (libsource (lib "eagle-import") (part "R2512"))
    )
    (comp (ref "C10")
      (value "10n")
      (footprint "eagle-import:C0603")
      (libsource (lib "eagle-import") (part "C0603"))
    )
    (comp (ref "C11")
      (value "10n")
      (footprint "eagle-import:C0603")
      (libsource (lib "eagle-import") (part "C0603"))
    )
    (comp (ref "C12")
      (value "1u")
      (footprint "eagle-import:C0603")
      (libsource (lib "eagle-import") (part "C0603"))
    )
    (comp (ref "C13")
      (value "1u")
      (footprint "eagle-import:C0603")
      (libsource (lib "eagle-import") (part "C0603"))
    )
    (comp (ref "C14")
      (value "18p")
      (footprint "eagle-import:C0603")
      (libsource (lib "eagle-import") (part "C0603"))
    )
    (comp (ref "C15")
      (value "18p")
      (footprint "eagle-import:C0603")
      (libsource (lib "eagle-import") (part "C0603"))
    )
    (comp (ref "C16")
      (value "10n")
      (footprint "eagle-import:C0603")
      (libsource (lib "eagle-import") (part "C0603"))
    )
    (comp (ref "C17")
      (value "10n")
      (footprint "eagle-import:C0603")
      (libsource (lib "eagle-import") (part "C0603"))
    )
    (comp (ref "C22")
      (value "100n")
      (footprint "eagle-import:C0603")
      (libsource (lib "eagle-import") (part "C0603"))
    )
    (comp (ref "C23")
      (value "100n")
      (footprint "eagle-import:C0603")
      (libsource (lib "eagle-import") (part "C0603"))
    )
    (comp (ref "C24")
      (value "100n")
      (footprint "eagle-import:C0603")
      (libsource (lib "eagle-import") (part "C0603"))
    )
    (comp (ref "C25")
      (value "100n")
      (footprint "eagle-import:C0603")
      (libsource (lib "eagle-import") (part "C0603"))
    )
    (comp (ref "IC1")
      (value "LPC11C1X")
      (footprint "eagle-import:LQFP48")
      (libsource (lib "eagle-import") (part "LPC11C1X"))
    )
    (comp (ref "JP1")
      (value "PINHD-1X6")
      (footprint "eagle-import:1X06")
      (libsource (lib "eagle-import") (part "PINHD-1X6"))
    )
    (comp (ref "L6")
      (value "WE-CBF_0603")
      (footprint "eagle-import:0603")
      (libsource (lib "eagle-import") (part "WE-CBF_0603"))
    )
    (comp (ref "LED2")
      (value "LEDCHIPLED_1206")
      (footprint "eagle-import:CHIPLED_1206")
      (libsource (lib "eagle-import") (part "LEDCHIPLED_1206"))
    )
    (comp (ref "LED3")
      (value "LEDCHIPLED_1206")
      (footprint "eagle-import:CHIPLED_1206")
      (libsource (lib "eagle-import") (part "LEDCHIPLED_1206"))
    )
    (comp (ref "Q3")
      (value "2N7002")
      (footprint "eagle-import:SOT23")
      (libsource (lib "eagle-import") (part "2N7002"))
    )
    (comp (ref "Q4")
      (value "2N7002")
      (footprint "eagle-import:SOT23")
      (libsource (lib "eagle-import") (part "2N7002"))
    )
    (comp (ref "R1")
      (value "100")
      (footprint "eagle-import:R0603")
      (libsource (lib "eagle-import") (part "R0603"))
    )
    (comp (ref "R3")
      (value "100")
      (footprint "eagle-import:R0603")
      (libsource (lib "eagle-import") (part "R0603"))
    )
    (comp (ref "R4")
      (value "100")
      (footprint "eagle-import:R0603")
      (libsource (lib "eagle-import") (part "R0603"))
    )
    (comp (ref "R5")
      (value "100")
      (footprint "eagle-import:R0603")
      (libsource (lib "eagle-import") (part "R0603"))
    )
    (comp (ref "R6")
      (value "100")
      (footprint "eagle-import:R0603")
      (libsource (lib "eagle-import") (part "R0603"))
    )
    (comp (ref "R7")
      (value "100")
      (footprint "eagle-import:R0603")
      (libsource (lib "eagle-import") (part "R0603"))
    )
    (comp (ref "R8")
      (value "R0603")
      (footprint "eagle-import:R0603")
      (libsource (lib "eagle-import") (part "R0603"))
    )
    (comp (ref "R9")
      (value "R0603")
      (footprint "eagle-import:R0603")
      (libsource (lib "eagle-import") (part "R0603"))
    )
    (comp (ref "R10")
      (value "140")
      (footprint "eagle-import:R1206")
      (libsource (lib "eagle-import") (part "R-EU_R1206"))
    )
    (comp (ref "R11")
      (value "140")
      (footprint "eagle-import:R1206")
      (libsource (lib "eagle-import") (part "R-EU_R1206"))
    )
    (comp (ref "R15")
      (value "R0603")
      (footprint "eagle-import:R0603")
      (libsource (lib "eagle-import") (part "R0603"))
    )
    (comp (ref "R16")
      (value "R0603")
      (footprint "eagle-import:R0603")
      (libsource (lib "eagle-import") (part "R0603"))
    )
    (comp (ref "Y1")
      (value "CRYSTALTHIN")
      (footprint "eagle-import:CRYSTAL_3.2X2.5")
      (libsource (lib "eagle-import") (part "CRYSTALTHIN"))
    )
    (comp (ref "C1")
      (value "22u")
      (footprint "eagle-import:PANASONIC_F")
      (libsource (lib "eagle-import") (part "CPOLEF"))
    )
    (comp (ref "CFSM")
      (value "1u")
      (footprint "eagle-import:C0603")
      (libsource (lib "eagle-import") (part "C0603"))
    )
    (comp (ref "CV")
      (value "10n")
      (footprint "eagle-import:C1206")
      (libsource (lib "eagle-import") (part "C1206"))
    )
    (comp (ref "CVREF")
      (value "1u")
      (footprint "eagle-import:C0603")
      (libsource (lib "eagle-import") (part "C0603"))
    )
    (comp (ref "CVREG")
      (value "1u")
      (footprint "eagle-import:C0603")
      (libsource (lib "eagle-import") (part "C0603"))
    )
    (comp (ref "D1")
      (value "56V")
      (footprint "eagle-import:SOD123")
      (libsource (lib "eagle-import") (part "DIODE-SOD123"))
    )
    (comp (ref "D2")
      (value "12V")
      (footprint "eagle-import:SOD323-R")
      (libsource (lib "eagle-import") (part "DIODE-SOD323-R"))
    )
    (comp (ref "IC2")
      (value "LTC6803-4")
      (footprint "eagle-import:44SSOP")
      (libsource (lib "eagle-import") (part "LTC6803-4"))
    )
    (comp (ref "L7")
      (value "WE-CBF_1206")
      (footprint "eagle-import:1206")
      (libsource (lib "eagle-import") (part "WE-CBF_1206"))
    )
    (comp (ref "Q1")
      (value "TP0610K")
      (footprint "eagle-import:SOT23")
      (libsource (lib "eagle-import") (part "TP0610K"))
    )
    (comp (ref "Q2")
      (value "2N7002")
      (footprint "eagle-import:SOT23")
      (libsource (lib "eagle-import") (part "2N7002"))
    )
    (comp (ref "R2")
      (value "1M")
      (footprint "eagle-import:R0603")
      (libsource (lib "eagle-import") (part "R0603"))
    )
    (comp (ref "RCSB")
      (value "1M")
      (footprint "eagle-import:R0603")
      (libsource (lib "eagle-import") (part "R0603"))
    )
    (comp (ref "RCSB1")
      (value "1M")
      (footprint "eagle-import:R0603")
      (libsource (lib "eagle-import") (part "R0603"))
    )
    (comp (ref "RCSB2")
      (value "4.7k")
      (footprint "eagle-import:R0603")
      (libsource (lib "eagle-import") (part "R0603"))
    )
    (comp (ref "RCSB3")
      (value "1M")
      (footprint "eagle-import:R0603")
      (libsource (lib "eagle-import") (part "R0603"))
    )
    (comp (ref "RFSM1")
      (value "332k0.1%")
      (footprint "eagle-import:R0603")
      (libsource (lib "eagle-import") (part "R-EU_R0603"))
    )
    (comp (ref "RFSM2")
      (value "20k0.1%")
      (footprint "eagle-import:R0603")
      (libsource (lib "eagle-import") (part "R-EU_R0603"))
    )
    (comp (ref "RGQ1_1")
      (value "1M")
      (footprint "eagle-import:R0805")
      (libsource (lib "eagle-import") (part "R0805"))
    )
    (comp (ref "RGQ1_2")
      (value "100k")
      (footprint "eagle-import:R0805")
      (libsource (lib "eagle-import") (part "R0805"))
    )
    (comp (ref "RGQ1_3")
      (value "1M")
      (footprint "eagle-import:R0603")
      (libsource (lib "eagle-import") (part "R0603"))
    )
    (comp (ref "V+R")
      (value "100")
      (footprint "eagle-import:R0805")
      (libsource (lib "eagle-import") (part "R0805"))
    )
    (comp (ref "V-R")
      (value "100")
      (footprint "eagle-import:R0805")
      (libsource (lib "eagle-import") (part "R0805"))
    )
  )
  (nets
    (net (code "1") (name "+3V3") (class "Default")
      (node (ref "C27") (pin "1") (pinfunction "1_1") (pintype "passive"))
      (node (ref "C5") (pin "+") (pinfunction "+_+") (pintype "passive"))
      (node (ref "D4") (pin "C") (pinfunction "C_C") (pintype "passive"))
      (node (ref "IC2") (pin "30") (pinfunction "VTEMP2_30") (pintype "bidirectional"))
      (node (ref "JP1") (pin "1") (pinfunction "1_1") (pintype "passive"))
      (node (ref "L2") (pin "2") (pinfunction "2_2") (pintype "passive"))
      (node (ref "L5") (pin "2") (pinfunction "2_2") (pintype "passive"))
      (node (ref "L6") (pin "2") (pinfunction "2_2") (pintype "passive"))
      (node (ref "LED1") (pin "A") (pinfunction "A_A") (pintype "passive"))
      (node (ref "LED2") (pin "A") (pinfunction "A_A") (pintype "passive"))
      (node (ref "LED3") (pin "A") (pinfunction "A_A") (pintype "passive"))
      (node (ref "NTC_R0") (pin "2") (pinfunction "2_2") (pintype "passive"))
      (node (ref "NTC_R1") (pin "2") (pinfunction "2_2") (pintype "passive"))
      (node (ref "NTC_R2") (pin "2") (pinfunction "2_2") (pintype "passive"))
      (node (ref "NTC_R3") (pin "2") (pinfunction "2_2") (pintype "passive"))
      (node (ref "NTC_R4") (pin "2") (pinfunction "2_2") (pintype "passive"))
      (node (ref "NTC_R5") (pin "2") (pinfunction "2_2") (pintype "passive"))
      (node (ref "NTC_R6") (pin "2") (pinfunction "2_2") (pintype "passive"))
      (node (ref "NTC_R7") (pin "2") (pinfunction "2_2") (pintype "passive"))
      (node (ref "Q2") (pin "1") (pinfunction "G_1") (pintype "passive"))
      (node (ref "R8") (pin "1") (pinfunction "1_1") (pintype "passive"))
      (node (ref "R9") (pin "1") (pinfunction "1_1") (pintype "passive"))
      (node (ref "RGQ1_3") (pin "2") (pinfunction "2_2") (pintype "passive"))
    )
    (net (code "2") (name "ACTIVE_LED") (class "Default")
      (node (ref "IC1") (pin "48") (pinfunction "PIO3_3/~{RI}_48") (pintype "bidirectional"))
      (node (ref "R16") (pin "1") (pinfunction "1_1") (pintype "passive"))
    )
    (net (code "3") (name "AD0") (class "Default")
      (node (ref "IC1") (pin "32") (pinfunction "PIO0_11/AD0/CT32B0_MAT3_32") (pintype "bidirectional"))
      (node (ref "K5") (pin "14") (pinfunction "14_14") (pintype "bidirectional"))
      (node (ref "NTC_C0") (pin "1") (pinfunction "1_1") (pintype "passive"))
      (node (ref "NTC_R0") (pin "1") (pinfunction "1_1") (pintype "passive"))
    )
    (net (code "4") (name "AD1") (class "Default")
      (node (ref "IC1") (pin "33") (pinfunction "PIO1_0/AD1/CT32B1_CAP0_33") (pintype "bidirectional"))
      (node (ref "K5") (pin "13") (pinfunction "13_13") (pintype "bidirectional"))
      (node (ref "NTC_C1") (pin "1") (pinfunction "1_1") (pintype "passive"))
      (node (ref "NTC_R1") (pin "1") (pinfunction "1_1") (pintype "passive"))
    )
    (net (code "5") (name "AD2") (class "Default")
      (node (ref "IC1") (pin "34") (pinfunction "PIO1_1/AD2/CT32B1_MAT0_34") (pintype "bidirectional"))
      (node (ref "K5") (pin "12") (pinfunction "12_12") (pintype "bidirectional"))
      (node (ref "NTC_C2") (pin "1") (pinfunction "1_1") (pintype "passive"))
      (node (ref "NTC_R2") (pin "1") (pinfunction "1_1") (pintype "passive"))
    )
    (net (code "6") (name "AD3") (class "Default")
      (node (ref "IC1") (pin "35") (pinfunction "PIO1_2/AD3/CT32B1_MAT1_35") (pintype "bidirectional"))
      (node (ref "K5") (pin "11") (pinfunction "11_11") (pintype "bidirectional"))
      (node (ref "NTC_C3") (pin "1") (pinfunction "1_1") (pintype "passive"))
      (node (ref "NTC_R3") (pin "1") (pinfunction "1_1") (pintype "passive"))
    )
    (net (code "7") (name "AD4{slash}SWDIO") (class "Default")
      (node (ref "IC1") (pin "39") (pinfunction "PIO1_3/SWDIO/AD4/CT32B1_MAT2_39") (pintype "bidirectional"))
      (node (ref "JP1") (pin "4") (pinfunction "4_4") (pintype "passive"))
      (node (ref "K5") (pin "10") (pinfunction "10_10") (pintype "bidirectional"))
      (node (ref "NTC_C4") (pin "1") (pinfunction "1_1") (pintype "passive"))
      (node (ref "NTC_R4") (pin "1") (pinfunction "1_1") (pintype "passive"))
    )
    (net (code "8") (name "AD5") (class "Default")
      (node (ref "IC1") (pin "40") (pinfunction "PIO1_4/AD5/CT32B1_MAT3_40") (pintype "bidirectional"))
      (node (ref "K5") (pin "9") (pinfunction "9_9") (pintype "bidirectional"))
      (node (ref "NTC_C5") (pin "1") (pinfunction "1_1") (pintype "passive"))
      (node (ref "NTC_R5") (pin "1") (pinfunction "1_1") (pintype "passive"))
    )
    (net (code "9") (name "AD6") (class "Default")
      (node (ref "IC1") (pin "30") (pinfunction "PIO1_10/AD6/CT16B1_MAT1_30") (pintype "bidirectional"))
      (node (ref "NTC_C6") (pin "1") (pinfunction "1_1") (pintype "passive"))
      (node (ref "NTC_R6") (pin "1") (pinfunction "1_1") (pintype "passive"))
    )
    (net (code "10") (name "AD7") (class "Default")
      (node (ref "IC1") (pin "42") (pinfunction "PIO1_11/AD7_42") (pintype "bidirectional"))
      (node (ref "K5") (pin "8") (pinfunction "8_8") (pintype "bidirectional"))
      (node (ref "NTC_C7") (pin "1") (pinfunction "1_1") (pintype "passive"))
      (node (ref "NTC_R7") (pin "1") (pinfunction "1_1") (pintype "passive"))
    )
    (net (code "11") (name "BAL1") (class "Default")
      (node (ref "IC2") (pin "25") (pinfunction "S1_25") (pintype "bidirectional"))
      (node (ref "RBG1") (pin "2") (pinfunction "2_2") (pintype "passive"))
    )
    (net (code "12") (name "BAL2") (class "Default")
      (node (ref "IC2") (pin "23") (pinfunction "S2_23") (pintype "bidirectional"))
      (node (ref "RBG2") (pin "2") (pinfunction "2_2") (pintype "passive"))
    )
    (net (code "13") (name "BAL3") (class "Default")
      (node (ref "IC2") (pin "21") (pinfunction "S3_21") (pintype "bidirectional"))
      (node (ref "RBG3") (pin "2") (pinfunction "2_2") (pintype "passive"))
    )
    (net (code "14") (name "BAL4") (class "Default")
      (node (ref "IC2") (pin "19") (pinfunction "S4_19") (pintype "bidirectional"))
      (node (ref "RBG4") (pin "2") (pinfunction "2_2") (pintype "passive"))
    )
    (net (code "15") (name "BAL5") (class "Default")
      (node (ref "IC2") (pin "17") (pinfunction "S5_17") (pintype "bidirectional"))
      (node (ref "RBG5") (pin "2") (pinfunction "2_2") (pintype "passive"))
    )
    (net (code "16") (name "BAL6") (class "Default")
      (node (ref "IC2") (pin "15") (pinfunction "S6_15") (pintype "bidirectional"))
      (node (ref "RBG6") (pin "2") (pinfunction "2_2") (pintype "passive"))
    )
    (net (code "17") (name "BAL7") (class "Default")
      (node (ref "IC2") (pin "13") (pinfunction "S7_13") (pintype "bidirectional"))
      (node (ref "RBG7") (pin "2") (pinfunction "2_2") (pintype "passive"))
    )
    (net (code "18") (name "BAL8") (class "Default")
      (node (ref "IC2") (pin "11") (pinfunction "S8_11") (pintype "bidirectional"))
      (node (ref "RBG8") (pin "2") (pinfunction "2_2") (pintype "passive"))
    )
    (net (code "19") (name "BAL9") (class "Default")
      (node (ref "IC2") (pin "9") (pinfunction "S9_9") (pintype "bidirectional"))
      (node (ref "RBG9") (pin "2") (pinfunction "2_2") (pintype "passive"))
    )
    (net (code "20") (name "BAL10") (class "Default")
      (node (ref "IC2") (pin "7") (pinfunction "S10_7") (pintype "bidirectional"))
      (node (ref "RBG10") (pin "2") (pinfunction "2_2") (pintype "passive"))
    )
    (net (code "21") (name "BAL11") (class "Default")
      (node (ref "IC2") (pin "5") (pinfunction "S11_5") (pintype "bidirectional"))
      (node (ref "RBG11") (pin "2") (pinfunction "2_2") (pintype "passive"))
    )
    (net (code "22") (name "BAL12") (class "Default")
      (node (ref "IC2") (pin "3") (pinfunction "S12_3") (pintype "bidirectional"))
      (node (ref "RBG12") (pin "2") (pinfunction "2_2") (pintype "passive"))
    )
    (net (code "23") (name "C0") (class "Default")
      (node (ref "CCM1") (pin "2") (pinfunction "2_2") (pintype "passive"))
      (node (ref "DCM1") (pin "A") (pinfunction "A_A") (pintype "passive"))
      (node (ref "IC2") (pin "26") (pinfunction "C0_26") (pintype "bidirectional"))
      (node (ref "K1") (pin "1") (pinfunction "1_1") (pintype "bidirectional"))
      (node (ref "K1") (pin "8") (pinfunction "8_8") (pintype "bidirectional"))
      (node (ref "RP1") (pin "1") (pinfunction "1_1") (pintype "passive"))
      (node (ref "V-R") (pin "1") (pinfunction "1_1") (pintype "passive"))
    )
    (net (code "24") (name "C1") (class "Default")
      (node (ref "K1") (pin "9") (pinfunction "9_9") (pintype "bidirectional"))
      (node (ref "QB1") (pin "2") (pinfunction "S_2") (pintype "passive"))
      (node (ref "RCM1") (pin "1") (pinfunction "1_1") (pintype "passive"))
      (node (ref "RP2") (pin "1") (pinfunction "1_1") (pintype "passive"))
    )
    (net (code "25") (name "C1M") (class "Default")
      (node (ref "CCM1") (pin "1") (pinfunction "1_1") (pintype "passive"))
      (node (ref "CCM2") (pin "2") (pinfunction "2_2") (pintype "passive"))
      (node (ref "DCM1") (pin "C") (pinfunction "C_C") (pintype "passive"))
      (node (ref "DCM2") (pin "A") (pinfunction "A_A") (pintype "passive"))
      (node (ref "IC2") (pin "24") (pinfunction "C1_24") (pintype "bidirectional"))
      (node (ref "RCM1") (pin "2") (pinfunction "2_2") (pintype "passive"))
    )
    (net (code "26") (name "C2") (class "Default")
      (node (ref "K1") (pin "2") (pinfunction "2_2") (pintype "bidirectional"))
      (node (ref "QB2") (pin "2") (pinfunction "S_2") (pintype "passive"))
      (node (ref "RCM2") (pin "1") (pinfunction "1_1") (pintype "passive"))
      (node (ref "RP3") (pin "1") (pinfunction "1_1") (pintype "passive"))
    )
    (net (code "27") (name "C2M") (class "Default")
      (node (ref "CCM2") (pin "1") (pinfunction "1_1") (pintype "passive"))
      (node (ref "CCM3") (pin "2") (pinfunction "2_2") (pintype "passive"))
      (node (ref "DCM2") (pin "C") (pinfunction "C_C") (pintype "passive"))
      (node (ref "DCM3") (pin "A") (pinfunction "A_A") (pintype "passive"))
      (node (ref "IC2") (pin "22") (pinfunction "C2_22") (pintype "bidirectional"))
      (node (ref "RCM2") (pin "2") (pinfunction "2_2") (pintype "passive"))
    )
    (net (code "28") (name "C3") (class "Default")
      (node (ref "K1") (pin "10") (pinfunction "10_10") (pintype "bidirectional"))
      (node (ref "QB3") (pin "2") (pinfunction "S_2") (pintype "passive"))
      (node (ref "RCM3") (pin "1") (pinfunction "1_1") (pintype "passive"))
      (node (ref "RP4") (pin "1") (pinfunction "1_1") (pintype "passive"))
    )
    (net (code "29") (name "C3M") (class "Default")
      (node (ref "CCM3") (pin "1") (pinfunction "1_1") (pintype "passive"))
      (node (ref "CCM4") (pin "2") (pinfunction "2_2") (pintype "passive"))
      (node (ref "DCM3") (pin "C") (pinfunction "C_C") (pintype "passive"))
      (node (ref "DCM4") (pin "A") (pinfunction "A_A") (pintype "passive"))
      (node (ref "IC2") (pin "20") (pinfunction "C3_20") (pintype "bidirectional"))
      (node (ref "RCM3") (pin "2") (pinfunction "2_2") (pintype "passive"))
    )
    (net (code "30") (name "C4") (class "Default")
      (node (ref "K1") (pin "3") (pinfunction "3_3") (pintype "bidirectional"))
      (node (ref "QB4") (pin "2") (pinfunction "S_2") (pintype "passive"))
      (node (ref "RCM4") (pin "1") (pinfunction "1_1") (pintype "passive"))
      (node (ref "RP5") (pin "1") (pinfunction "1_1") (pintype "passive"))
    )
    (net (code "31") (name "C4M") (class "Default")
      (node (ref "CCM4") (pin "1") (pinfunction "1_1") (pintype "passive"))
      (node (ref "CCM5") (pin "2") (pinfunction "2_2") (pintype "passive"))
      (node (ref "DCM4") (pin "C") (pinfunction "C_C") (pintype "passive"))
      (node (ref "DCM5") (pin "A") (pinfunction "A_A") (pintype "passive"))
      (node (ref "IC2") (pin "18") (pinfunction "C4_18") (pintype "bidirectional"))
      (node (ref "RCM4") (pin "2") (pinfunction "2_2") (pintype "passive"))
    )
    (net (code "32") (name "C5") (class "Default")
      (node (ref "K1") (pin "11") (pinfunction "11_11") (pintype "bidirectional"))
      (node (ref "QB5") (pin "2") (pinfunction "S_2") (pintype "passive"))
      (node (ref "RCM5") (pin "1") (pinfunction "1_1") (pintype "passive"))
      (node (ref "RP6") (pin "1") (pinfunction "1_1") (pintype "passive"))
    )
    (net (code "33") (name "C5M") (class "Default")
      (node (ref "CCM5") (pin "1") (pinfunction "1_1") (pintype "passive"))
      (node (ref "CCM6") (pin "2") (pinfunction "2_2") (pintype "passive"))
      (node (ref "DCM5") (pin "C") (pinfunction "C_C") (pintype "passive"))
      (node (ref "DCM6") (pin "A") (pinfunction "A_A") (pintype "passive"))
      (node (ref "IC2") (pin "16") (pinfunction "C5_16") (pintype "bidirectional"))
      (node (ref "RCM5") (pin "2") (pinfunction "2_2") (pintype "passive"))
    )
    (net (code "34") (name "C6") (class "Default")
      (node (ref "K1") (pin "4") (pinfunction "4_4") (pintype "bidirectional"))
      (node (ref "QB6") (pin "2") (pinfunction "S_2") (pintype "passive"))
      (node (ref "RCM6") (pin "1") (pinfunction "1_1") (pintype "passive"))
      (node (ref "RP7") (pin "1") (pinfunction "1_1") (pintype "passive"))
    )
    (net (code "35") (name "C6M") (class "Default")
      (node (ref "CCM6") (pin "1") (pinfunction "1_1") (pintype "passive"))
      (node (ref "CCM7") (pin "2") (pinfunction "2_2") (pintype "passive"))
      (node (ref "DCM6") (pin "C") (pinfunction "C_C") (pintype "passive"))
      (node (ref "DCM7") (pin "A") (pinfunction "A_A") (pintype "passive"))
      (node (ref "IC2") (pin "14") (pinfunction "C6_14") (pintype "bidirectional"))
      (node (ref "RCM6") (pin "2") (pinfunction "2_2") (pintype "passive"))
    )
    (net (code "36") (name "C7") (class "Default")
      (node (ref "K1") (pin "12") (pinfunction "12_12") (pintype "bidirectional"))
      (node (ref "QB7") (pin "2") (pinfunction "S_2") (pintype "passive"))
      (node (ref "RCM7") (pin "1") (pinfunction "1_1") (pintype "passive"))
      (node (ref "RP8") (pin "1") (pinfunction "1_1") (pintype "passive"))
    )
    (net (code "37") (name "C7M") (class "Default")
      (node (ref "CCM7") (pin "1") (pinfunction "1_1") (pintype "passive"))
      (node (ref "CCM8") (pin "2") (pinfunction "2_2") (pintype "passive"))
      (node (ref "DCM7") (pin "C") (pinfunction "C_C") (pintype "passive"))
      (node (ref "DCM8") (pin "A") (pinfunction "A_A") (pintype "passive"))
      (node (ref "IC2") (pin "12") (pinfunction "C7_12") (pintype "bidirectional"))
      (node (ref "RCM7") (pin "2") (pinfunction "2_2") (pintype "passive"))
    )
    (net (code "38") (name "C8") (class "Default")
      (node (ref "K1") (pin "5") (pinfunction "5_5") (pintype "bidirectional"))
      (node (ref "QB8") (pin "2") (pinfunction "S_2") (pintype "passive"))
      (node (ref "RCM8") (pin "1") (pinfunction "1_1") (pintype "passive"))
      (node (ref "RP9") (pin "1") (pinfunction "1_1") (pintype "passive"))
    )
    (net (code "39") (name "C8M") (class "Default")
      (node (ref "CCM8") (pin "1") (pinfunction "1_1") (pintype "passive"))
      (node (ref "CCM9") (pin "2") (pinfunction "2_2") (pintype "passive"))
      (node (ref "DCM8") (pin "C") (pinfunction "C_C") (pintype "passive"))
      (node (ref "DCM9") (pin "A") (pinfunction "A_A") (pintype "passive"))
      (node (ref "IC2") (pin "10") (pinfunction "C8_10") (pintype "bidirectional"))
      (node (ref "RCM8") (pin "2") (pinfunction "2_2") (pintype "passive"))
    )
    (net (code "40") (name "C9") (class "Default")
      (node (ref "K1") (pin "13") (pinfunction "13_13") (pintype "bidirectional"))
      (node (ref "QB9") (pin "2") (pinfunction "S_2") (pintype "passive"))
      (node (ref "RCM9") (pin "1") (pinfunction "1_1") (pintype "passive"))
      (node (ref "RP10") (pin "1") (pinfunction "1_1") (pintype "passive"))
    )
    (net (code "41") (name "C9M") (class "Default")
      (node (ref "CCM10") (pin "2") (pinfunction "2_2") (pintype "passive"))
      (node (ref "CCM9") (pin "1") (pinfunction "1_1") (pintype "passive"))
      (node (ref "DCM10") (pin "A") (pinfunction "A_A") (pintype "passive"))
      (node (ref "DCM9") (pin "C") (pinfunction "C_C") (pintype "passive"))
      (node (ref "IC2") (pin "8") (pinfunction "C9_8") (pintype "bidirectional"))
      (node (ref "RCM9") (pin "2") (pinfunction "2_2") (pintype "passive"))
    )
    (net (code "42") (name "C10") (class "Default")
      (node (ref "K1") (pin "6") (pinfunction "6_6") (pintype "bidirectional"))
      (node (ref "QB10") (pin "2") (pinfunction "S_2") (pintype "passive"))
      (node (ref "RCM10") (pin "1") (pinfunction "1_1") (pintype "passive"))
      (node (ref "RP11") (pin "1") (pinfunction "1_1") (pintype "passive"))
    )
    (net (code "43") (name "C10M") (class "Default")
      (node (ref "CCM10") (pin "1") (pinfunction "1_1") (pintype "passive"))
      (node (ref "CCM11") (pin "2") (pinfunction "2_2") (pintype "passive"))
      (node (ref "DCM10") (pin "C") (pinfunction "C_C") (pintype "passive"))
      (node (ref "DCM11") (pin "A") (pinfunction "A_A") (pintype "passive"))
      (node (ref "IC2") (pin "6") (pinfunction "C10_6") (pintype "bidirectional"))
      (node (ref "RCM10") (pin "2") (pinfunction "2_2") (pintype "passive"))
    )
    (net (code "44") (name "C11") (class "Default")
      (node (ref "K1") (pin "14") (pinfunction "14_14") (pintype "bidirectional"))
      (node (ref "QB11") (pin "2") (pinfunction "S_2") (pintype "passive"))
      (node (ref "RCM11") (pin "1") (pinfunction "1_1") (pintype "passive"))
      (node (ref "RP12") (pin "1") (pinfunction "1_1") (pintype "passive"))
    )
    (net (code "45") (name "C11M") (class "Default")
      (node (ref "CCM11") (pin "1") (pinfunction "1_1") (pintype "passive"))
      (node (ref "CCM12") (pin "2") (pinfunction "2_2") (pintype "passive"))
      (node (ref "DCM11") (pin "C") (pinfunction "C_C") (pintype "passive"))
      (node (ref "DCM12") (pin "A") (pinfunction "A_A") (pintype "passive"))
      (node (ref "IC2") (pin "4") (pinfunction "C11_4") (pintype "bidirectional"))
      (node (ref "RCM11") (pin "2") (pinfunction "2_2") (pintype "passive"))
    )
    (net (code "46") (name "C12") (class "Default")
      (node (ref "K1") (pin "7") (pinfunction "7_7") (pintype "bidirectional"))
      (node (ref "L7") (pin "1") (pinfunction "1_1") (pintype "passive"))
      (node (ref "QB12") (pin "2") (pinfunction "S_2") (pintype "passive"))
      (node (ref "RCM12") (pin "1") (pinfunction "1_1") (pintype "passive"))
    )
    (net (code "47") (name "C12M") (class "Default")
      (node (ref "CCM12") (pin "1") (pinfunction "1_1") (pintype "passive"))
      (node (ref "DCM12") (pin "C") (pinfunction "C_C") (pintype "passive"))
      (node (ref "IC2") (pin "2") (pinfunction "C12_2") (pintype "bidirectional"))
      (node (ref "RCM12") (pin "2") (pinfunction "2_2") (pintype "passive"))
    )
    (net (code "48") (name "CANH") (class "Default")
      (node (ref "K3") (pin "2") (pinfunction "2_2") (pintype "bidirectional"))
      (node (ref "K4") (pin "3") (pinfunction "3_3") (pintype "bidirectional"))
      (node (ref "L8") (pin "1") (pinfunction "3_1") (pintype "passive"))
    )
    (net (code "49") (name "CANL") (class "Default")
      (node (ref "K3") (pin "3") (pinfunction "3_3") (pintype "bidirectional"))
      (node (ref "K4") (pin "2") (pinfunction "2_2") (pintype "bidirectional"))
      (node (ref "L8") (pin "2") (pinfunction "1_2") (pintype "passive"))
    )
    (net (code "50") (name "CANRX") (class "Default")
      (node (ref "IC3") (pin "6") (pinfunction "O2_6") (pintype "bidirectional"))
      (node (ref "R7") (pin "2") (pinfunction "2_2") (pintype "passive"))
    )
    (net (code "51") (name "CANTX") (class "Default")
      (node (ref "IC3") (pin "7") (pinfunction "I1_7") (pintype "bidirectional"))
      (node (ref "R6") (pin "2") (pinfunction "2_2") (pintype "passive"))
    )
    (net (code "52") (name "CAR+12V") (class "Default")
      (node (ref "C28") (pin "1") (pinfunction "1_1") (pintype "passive"))
      (node (ref "C3") (pin "+") (pinfunction "+_+") (pintype "passive"))
      (node (ref "DCDC1") (pin "2") (pinfunction "VIN+_2") (pintype "bidirectional"))
      (node (ref "IC5") (pin "8") (pinfunction "VIN_8") (pintype "passive"))
      (node (ref "L1") (pin "2") (pinfunction "2_2") (pintype "passive"))
    )
    (net (code "53") (name "CAR+12VIN") (class "Default")
      (node (ref "C2") (pin "+") (pinfunction "+_+") (pintype "passive"))
      (node (ref "C29") (pin "1") (pinfunction "1_1") (pintype "passive"))
      (node (ref "K3") (pin "4") (pinfunction "4_4") (pintype "bidirectional"))
      (node (ref "K4") (pin "1") (pinfunction "1_1") (pintype "bidirectional"))
      (node (ref "L1") (pin "1") (pinfunction "1_1") (pintype "passive"))
    )
    (net (code "54") (name "CARGND") (class "Default")
      (node (ref "C18") (pin "2") (pinfunction "2_2") (pintype "passive"))
      (node (ref "C19") (pin "2") (pinfunction "2_2") (pintype "passive"))
      (node (ref "C2") (pin "-") (pinfunction "-_-") (pintype "passive"))
      (node (ref "C20") (pin "2") (pinfunction "2_2") (pintype "passive"))
      (node (ref "C28") (pin "2") (pinfunction "2_2") (pintype "passive"))
      (node (ref "C29") (pin "2") (pinfunction "2_2") (pintype "passive"))
      (node (ref "C3") (pin "-") (pinfunction "-_-") (pintype "passive"))
      (node (ref "C6") (pin "2") (pinfunction "2_2") (pintype "passive"))
      (node (ref "C7") (pin "2") (pinfunction "2_2") (pintype "passive"))
      (node (ref "C8") (pin "2") (pinfunction "2_2") (pintype "passive"))
      (node (ref "DCDC1") (pin "1") (pinfunction "VIN-_1") (pintype "bidirectional"))
      (node (ref "IC3") (pin "4") (pinfunction "GND1_4") (pintype "bidirectional"))
      (node (ref "IC4") (pin "2") (pinfunction "VSS_2") (pintype "bidirectional"))
      (node (ref "IC5") (pin "2") (pinfunction "GND_2") (pintype "power_in"))
      (node (ref "IC5") (pin "3") (pinfunction "GND_3") (pintype "power_in"))
      (node (ref "IC5") (pin "6") (pinfunction "GND_6") (pintype "power_in"))
      (node (ref "IC5") (pin "7") (pinfunction "GND_7") (pintype "power_in"))
      (node (ref "K3") (pin "1") (pinfunction "1_1") (pintype "bidirectional"))
      (node (ref "K4") (pin "4") (pinfunction "4_4") (pintype "bidirectional"))
      (node (ref "R12") (pin "2") (pinfunction "2_2") (pintype "passive"))
    )
    (net (code "55") (name "CSB") (class "Default")
      (node (ref "IC2") (pin "44") (pinfunction "CSBI_44") (pintype "bidirectional"))
      (node (ref "R1") (pin "2") (pinfunction "2_2") (pintype "passive"))
      (node (ref "RCSB3") (pin "1") (pinfunction "1_1") (pintype "passive"))
    )
    (net (code "56") (name "DBGEN") (class "Default")
      (node (ref "C16") (pin "1") (pinfunction "1_1") (pintype "passive"))
      (node (ref "C25") (pin "1") (pinfunction "1_1") (pintype "passive"))
      (node (ref "IC1") (pin "28") (pinfunction "PIO0_9/MOSI0/CT16B0_MAT1_28") (pintype "bidirectional"))
      (node (ref "JP1") (pin "5") (pinfunction "5_5") (pintype "passive"))
      (node (ref "R8") (pin "2") (pinfunction "2_2") (pintype "passive"))
    )
    (net (code "57") (name "ERROR_LED") (class "Default")
      (node (ref "IC1") (pin "1") (pinfunction "PIO2_6_1") (pintype "bidirectional"))
      (node (ref "R15") (pin "1") (pinfunction "1_1") (pintype "passive"))
    )
    (net (code "58") (name "FSM") (class "Default")
      (node (ref "CFSM") (pin "2") (pinfunction "2_2") (pintype "passive"))
      (node (ref "IC2") (pin "29") (pinfunction "VTEMP1_29") (pintype "bidirectional"))
      (node (ref "RFSM1") (pin "1") (pinfunction "1_1") (pintype "passive"))
      (node (ref "RFSM2") (pin "2") (pinfunction "2_2") (pintype "passive"))
    )
    (net (code "59") (name "GND") (class "Default")
      (node (ref "C1") (pin "-") (pinfunction "-_-") (pintype "passive"))
      (node (ref "C10") (pin "2") (pinfunction "2_2") (pintype "passive"))
      (node (ref "C11") (pin "2") (pinfunction "2_2") (pintype "passive"))
      (node (ref "C12") (pin "2") (pinfunction "2_2") (pintype "passive"))
      (node (ref "C13") (pin "2") (pinfunction "2_2") (pintype "passive"))
      (node (ref "C14") (pin "1") (pinfunction "1_1") (pintype "passive"))
      (node (ref "C15") (pin "1") (pinfunction "1_1") (pintype "passive"))
      (node (ref "C16") (pin "2") (pinfunction "2_2") (pintype "passive"))
      (node (ref "C17") (pin "2") (pinfunction "2_2") (pintype "passive"))
      (node (ref "C21") (pin "2") (pinfunction "2_2") (pintype "passive"))
      (node (ref "C22") (pin "2") (pinfunction "2_2") (pintype "passive"))
      (node (ref "C23") (pin "2") (pinfunction "2_2") (pintype "passive"))
      (node (ref "C24") (pin "2") (pinfunction "2_2") (pintype "passive"))
      (node (ref "C25") (pin "2") (pinfunction "2_2") (pintype "passive"))
      (node (ref "C26") (pin "2") (pinfunction "2_2") (pintype "passive"))
      (node (ref "C27") (pin "2") (pinfunction "2_2") (pintype "passive"))
      (node (ref "C4") (pin "-") (pinfunction "-_-") (pintype "passive"))
      (node (ref "C5") (pin "-") (pinfunction "-_-") (pintype "passive"))
      (node (ref "C9") (pin "2") (pinfunction "2_2") (pintype "passive"))
      (node (ref "CFSM") (pin "1") (pinfunction "1_1") (pintype "passive"))
      (node (ref "CV") (pin "2") (pinfunction "2_2") (pintype "passive"))
      (node (ref "CVREF") (pin "1") (pinfunction "1_1") (pintype "passive"))
      (node (ref "CVREG") (pin "1") (pinfunction "1_1") (pintype "passive"))
      (node (ref "D1") (pin "A") (pinfunction "A_A") (pintype "passive"))
      (node (ref "D4") (pin "A") (pinfunction "A_A") (pintype "passive"))
      (node (ref "DCDC1") (pin "4") (pinfunction "VOUT-_4") (pintype "bidirectional"))
      (node (ref "IC1") (pin "41") (pinfunction "VSS_41") (pintype "bidirectional"))
      (node (ref "IC1") (pin "5") (pinfunction "VSS_5") (pintype "bidirectional"))
      (node (ref "IC2") (pin "27") (pinfunction "V-_27") (pintype "bidirectional"))
      (node (ref "IC2") (pin "33") (pinfunction "TOS_33") (pintype "bidirectional"))
      (node (ref "IC2") (pin "35") (pinfunction "GPIO1_35") (pintype "bidirectional"))
      (node (ref "IC2") (pin "36") (pinfunction "GPIO2_36") (pintype "bidirectional"))
      (node (ref "IC2") (pin "37") (pinfunction "A0_37") (pintype "bidirectional"))
      (node (ref "IC2") (pin "38") (pinfunction "A1_38") (pintype "bidirectional"))
      (node (ref "IC2") (pin "39") (pinfunction "A2_39") (pintype "bidirectional"))
      (node (ref "IC2") (pin "40") (pinfunction "A3_40") (pintype "bidirectional"))
      (node (ref "IC3") (pin "5") (pinfunction "GND2_5") (pintype "bidirectional"))
      (node (ref "JP1") (pin "6") (pinfunction "6_6") (pintype "passive"))
      (node (ref "K5") (pin "1") (pinfunction "1_1") (pintype "bidirectional"))
      (node (ref "K5") (pin "2") (pinfunction "2_2") (pintype "bidirectional"))
      (node (ref "K5") (pin "3") (pinfunction "3_3") (pintype "bidirectional"))
      (node (ref "K5") (pin "4") (pinfunction "4_4") (pintype "bidirectional"))
      (node (ref "K5") (pin "5") (pinfunction "5_5") (pintype "bidirectional"))
      (node (ref "K5") (pin "6") (pinfunction "6_6") (pintype "bidirectional"))
      (node (ref "K5") (pin "7") (pinfunction "7_7") (pintype "bidirectional"))
      (node (ref "NTC_C0") (pin "2") (pinfunction "2_2") (pintype "passive"))
      (node (ref "NTC_C1") (pin "2") (pinfunction "2_2") (pintype "passive"))
      (node (ref "NTC_C2") (pin "2") (pinfunction "2_2") (pintype "passive"))
      (node (ref "NTC_C3") (pin "2") (pinfunction "2_2") (pintype "passive"))
      (node (ref "NTC_C4") (pin "2") (pinfunction "2_2") (pintype "passive"))
      (node (ref "NTC_C5") (pin "2") (pinfunction "2_2") (pintype "passive"))
      (node (ref "NTC_C6") (pin "2") (pinfunction "2_2") (pintype "passive"))
      (node (ref "NTC_C7") (pin "2") (pinfunction "2_2") (pintype "passive"))
      (node (ref "Q2") (pin "2") (pinfunction "S_2") (pintype "passive"))
      (node (ref "Q3") (pin "2") (pinfunction "S_2") (pintype "passive"))
      (node (ref "Q4") (pin "2") (pinfunction "S_2") (pintype "passive"))
      (node (ref "R38") (pin "2") (pinfunction "2_2") (pintype "passive"))
      (node (ref "RFSM2") (pin "1") (pinfunction "1_1") (pintype "passive"))
      (node (ref "RGQ1_3") (pin "1") (pinfunction "1_1") (pintype "passive"))
      (node (ref "V-R") (pin "2") (pinfunction "2_2") (pintype "passive"))
    )
    (net (code "60") (name "ISP_CAN") (class "Default")
      (node (ref "IC1") (pin "14") (pinfunction "PIO0_3_14") (pintype "bidirectional"))
    )
    (net (code "61") (name "ISP_ENTER") (class "Default")
      (node (ref "IC1") (pin "4") (pinfunction "PIO0_1/CLKOUT/CT32B0_MAT2_4") (pintype "bidirectional"))
    )
    (net (code "62") (name "Net-(C10-Pad1)") (class "Default")
      (node (ref "C10") (pin "1") (pinfunction "1_1") (pintype "passive"))
      (node (ref "C11") (pin "1") (pinfunction "1_1") (pintype "passive"))
      (node (ref "C12") (pin "1") (pinfunction "1_1") (pintype "passive"))
      (node (ref "C13") (pin "1") (pinfunction "1_1") (pintype "passive"))
      (node (ref "C22") (pin "1") (pinfunction "1_1") (pintype "passive"))
      (node (ref "C23") (pin "1") (pinfunction "1_1") (pintype "passive"))
      (node (ref "IC1") (pin "44") (pinfunction "VDD_44") (pintype "bidirectional"))
      (node (ref "IC1") (pin "8") (pinfunction "VDD_8") (pintype "bidirectional"))
      (node (ref "L6") (pin "1") (pinfunction "1_1") (pintype "passive"))
    )
    (net (code "63") (name "Net-(DCDC1-VOUT+)") (class "Default")
      (node (ref "C26") (pin "1") (pinfunction "1_1") (pintype "passive"))
      (node (ref "C4") (pin "+") (pinfunction "+_+") (pintype "passive"))
      (node (ref "DCDC1") (pin "5") (pinfunction "VOUT+_5") (pintype "bidirectional"))
      (node (ref "L2") (pin "1") (pinfunction "1_1") (pintype "passive"))
    )
    (net (code "64") (name "Net-(IC1-CANRX)") (class "Default")
      (node (ref "IC1") (pin "19") (pinfunction "CANRX_19") (pintype "bidirectional"))
      (node (ref "R7") (pin "1") (pinfunction "1_1") (pintype "passive"))
    )
    (net (code "65") (name "Net-(IC1-CANTX)") (class "Default")
      (node (ref "IC1") (pin "20") (pinfunction "CANTX_20") (pintype "bidirectional"))
      (node (ref "R6") (pin "1") (pinfunction "1_1") (pintype "passive"))
    )
    (net (code "66") (name "Net-(IC1-PIO2_0{slash}~{DTR}{slash}SSEL1)") (class "Default")
      (node (ref "IC1") (pin "2") (pinfunction "PIO2_0/~{DTR}/SSEL1_2") (pintype "bidirectional"))
      (node (ref "R1") (pin "1") (pinfunction "1_1") (pintype "passive"))
    )
    (net (code "67") (name "Net-(IC1-PIO2_1{slash}~{DSR}{slash}SCK1)") (class "Default")
      (node (ref "IC1") (pin "13") (pinfunction "PIO2_1/~{DSR}/SCK1_13") (pintype "bidirectional"))
      (node (ref "R3") (pin "1") (pinfunction "1_1") (pintype "passive"))
    )
    (net (code "68") (name "Net-(IC1-PIO2_2{slash}~{DCD}{slash}MISO1)") (class "Default")
      (node (ref "IC1") (pin "26") (pinfunction "PIO2_2/~{DCD}/MISO1_26") (pintype "bidirectional"))
      (node (ref "R4") (pin "1") (pinfunction "1_1") (pintype "passive"))
    )
    (net (code "69") (name "Net-(IC1-PIO2_3{slash}~{RI}{slash}MOSI1)") (class "Default")
      (node (ref "IC1") (pin "38") (pinfunction "PIO2_3/~{RI}/MOSI1_38") (pintype "bidirectional"))
      (node (ref "R5") (pin "1") (pinfunction "1_1") (pintype "passive"))
    )
    (net (code "70") (name "Net-(IC1-XTALIN)") (class "Default")
      (node (ref "C15") (pin "2") (pinfunction "2_2") (pintype "passive"))
      (node (ref "IC1") (pin "6") (pinfunction "XTALIN_6") (pintype "bidirectional"))
      (node (ref "Y1") (pin "2") (pinfunction "2_2") (pintype "passive"))
    )
    (net (code "71") (name "Net-(IC1-XTALOUT)") (class "Default")
      (node (ref "C14") (pin "2") (pinfunction "2_2") (pintype "passive"))
      (node (ref "IC1") (pin "7") (pinfunction "XTALOUT_7") (pintype "bidirectional"))
      (node (ref "Y1") (pin "1") (pinfunction "1_1") (pintype "passive"))
    )
    (net (code "72") (name "Net-(IC2-WDTB)") (class "Default")
      (node (ref "IC2") (pin "34") (pinfunction "WDTB_34") (pintype "bidirectional"))
      (node (ref "R2") (pin "1") (pinfunction "1_1") (pintype "passive"))
    )
    (net (code "73") (name "Net-(IC3-I2)") (class "Default")
      (node (ref "IC3") (pin "3") (pinfunction "I2_3") (pintype "bidirectional"))
      (node (ref "R14") (pin "2") (pinfunction "2_2") (pintype "passive"))
    )
    (net (code "74") (name "Net-(IC3-O1)") (class "Default")
      (node (ref "IC3") (pin "2") (pinfunction "O1_2") (pintype "bidirectional"))
      (node (ref "R13") (pin "2") (pinfunction "2_2") (pintype "passive"))
    )
    (net (code "75") (name "Net-(IC3-VDD1)") (class "Default")
      (node (ref "C18") (pin "1") (pinfunction "1_1") (pintype "passive"))
      (node (ref "C8") (pin "1") (pinfunction "1_1") (pintype "passive"))
      (node (ref "IC3") (pin "1") (pinfunction "VDD1_1") (pintype "bidirectional"))
      (node (ref "L4") (pin "1") (pinfunction "1_1") (pintype "passive"))
    )
    (net (code "76") (name "Net-(IC3-VDD2)") (class "Default")
      (node (ref "C21") (pin "1") (pinfunction "1_1") (pintype "passive"))
      (node (ref "C9") (pin "1") (pinfunction "1_1") (pintype "passive"))
      (node (ref "IC3") (pin "8") (pinfunction "VDD2_8") (pintype "bidirectional"))
      (node (ref "L5") (pin "1") (pinfunction "1_1") (pintype "passive"))
    )
    (net (code "77") (name "Net-(IC4-CANH)") (class "Default")
      (node (ref "IC4") (pin "7") (pinfunction "CANH_7") (pintype "bidirectional"))
      (node (ref "L8") (pin "4") (pinfunction "4_4") (pintype "passive"))
    )
    (net (code "78") (name "Net-(IC4-CANL)") (class "Default")
      (node (ref "IC4") (pin "6") (pinfunction "CANL_6") (pintype "bidirectional"))
      (node (ref "L8") (pin "3") (pinfunction "2_3") (pintype "passive"))
    )
    (net (code "79") (name "Net-(IC4-RS)") (class "Default")
      (node (ref "IC4") (pin "8") (pinfunction "RS_8") (pintype "bidirectional"))
      (node (ref "R12") (pin "1") (pinfunction "1_1") (pintype "passive"))
    )
    (net (code "80") (name "Net-(IC4-RX)") (class "Default")
      (node (ref "IC4") (pin "4") (pinfunction "RX_4") (pintype "bidirectional"))
      (node (ref "R14") (pin "1") (pinfunction "1_1") (pintype "passive"))
    )
    (net (code "81") (name "Net-(IC4-TX)") (class "Default")
      (node (ref "IC4") (pin "1") (pinfunction "TX_1") (pintype "bidirectional"))
      (node (ref "R13") (pin "1") (pinfunction "1_1") (pintype "passive"))
    )
    (net (code "82") (name "Net-(IC4-VDD)") (class "Default")
      (node (ref "C6") (pin "1") (pinfunction "1_1") (pintype "passive"))
      (node (ref "C7") (pin "1") (pinfunction "1_1") (pintype "passive"))
      (node (ref "IC4") (pin "3") (pinfunction "VDD_3") (pintype "bidirectional"))
      (node (ref "L3") (pin "1") (pinfunction "1_1") (pintype "passive"))
    )
    (net (code "83") (name "Net-(IC5A-VOUT)") (class "Default")
      (node (ref "C19") (pin "1") (pinfunction "1_1") (pintype "passive"))
      (node (ref "C20") (pin "1") (pinfunction "1_1") (pintype "passive"))
      (node (ref "IC5") (pin "1") (pinfunction "VOUT_1") (pintype "output"))
      (node (ref "L3") (pin "2") (pinfunction "2_2") (pintype "passive"))
      (node (ref "L4") (pin "2") (pinfunction "2_2") (pintype "passive"))
    )
    (net (code "84") (name "Net-(L7-Pad2)") (class "Default")
      (node (ref "L7") (pin "2") (pinfunction "2_2") (pintype "passive"))
      (node (ref "V+R") (pin "1") (pinfunction "1_1") (pintype "passive"))
    )
    (net (code "85") (name "Net-(LED1-PadC)") (class "Default")
      (node (ref "LED1") (pin "C") (pinfunction "C_C") (pintype "passive"))
      (node (ref "R38") (pin "1") (pinfunction "1_1") (pintype "passive"))
    )
    (net (code "86") (name "Net-(LED2-PadC)") (class "Default")
      (node (ref "LED2") (pin "C") (pinfunction "C_C") (pintype "passive"))
      (node (ref "R10") (pin "1") (pinfunction "1_1") (pintype "passive"))
    )
    (net (code "87") (name "Net-(LED3-PadC)") (class "Default")
      (node (ref "LED3") (pin "C") (pinfunction "C_C") (pintype "passive"))
      (node (ref "R11") (pin "1") (pinfunction "1_1") (pintype "passive"))
    )
    (net (code "88") (name "Net-(Q1-G)") (class "Default")
      (node (ref "D2") (pin "A") (pinfunction "A_A") (pintype "passive"))
      (node (ref "Q1") (pin "1") (pinfunction "G_1") (pintype "passive"))
      (node (ref "RGQ1_1") (pin "2") (pinfunction "2_2") (pintype "passive"))
      (node (ref "RGQ1_2") (pin "2") (pinfunction "2_2") (pintype "passive"))
    )
    (net (code "89") (name "Net-(Q1-S)") (class "Default")
      (node (ref "D2") (pin "C") (pinfunction "C_C") (pintype "passive"))
      (node (ref "Q1") (pin "2") (pinfunction "S_2") (pintype "passive"))
      (node (ref "RGQ1_1") (pin "1") (pinfunction "1_1") (pintype "passive"))
      (node (ref "V+R") (pin "2") (pinfunction "2_2") (pintype "passive"))
    )
    (net (code "90") (name "Net-(Q2-D)") (class "Default")
      (node (ref "Q2") (pin "3") (pinfunction "D_3") (pintype "passive"))
      (node (ref "RGQ1_2") (pin "1") (pinfunction "1_1") (pintype "passive"))
    )
    (net (code "91") (name "Net-(Q3-D)") (class "Default")
      (node (ref "Q3") (pin "3") (pinfunction "D_3") (pintype "passive"))
      (node (ref "R10") (pin "2") (pinfunction "2_2") (pintype "passive"))
    )
    (net (code "92") (name "Net-(Q3-G)") (class "Default")
      (node (ref "Q3") (pin "1") (pinfunction "G_1") (pintype "passive"))
      (node (ref "R16") (pin "2") (pinfunction "2_2") (pintype "passive"))
    )
    (net (code "93") (name "Net-(Q4-D)") (class "Default")
      (node (ref "Q4") (pin "3") (pinfunction "D_3") (pintype "passive"))
      (node (ref "R11") (pin "2") (pinfunction "2_2") (pintype "passive"))
    )
    (net (code "94") (name "Net-(Q4-G)") (class "Default")
      (node (ref "Q4") (pin "1") (pinfunction "G_1") (pintype "passive"))
      (node (ref "R15") (pin "2") (pinfunction "2_2") (pintype "passive"))
    )
    (net (code "95") (name "Net-(QB1-D)") (class "Default")
      (node (ref "QB1") (pin "3") (pinfunction "D_3") (pintype "passive"))
      (node (ref "RP1") (pin "2") (pinfunction "2_2") (pintype "passive"))
    )
    (net (code "96") (name "Net-(QB1-G)") (class "Default")
      (node (ref "QB1") (pin "1") (pinfunction "G_1") (pintype "passive"))
      (node (ref "RBG1") (pin "1") (pinfunction "1_1") (pintype "passive"))
    )
    (net (code "97") (name "Net-(QB2-D)") (class "Default")
      (node (ref "QB2") (pin "3") (pinfunction "D_3") (pintype "passive"))
      (node (ref "RP2") (pin "2") (pinfunction "2_2") (pintype "passive"))
    )
    (net (code "98") (name "Net-(QB2-G)") (class "Default")
      (node (ref "QB2") (pin "1") (pinfunction "G_1") (pintype "passive"))
      (node (ref "RBG2") (pin "1") (pinfunction "1_1") (pintype "passive"))
    )
    (net (code "99") (name "Net-(QB3-D)") (class "Default")
      (node (ref "QB3") (pin "3") (pinfunction "D_3") (pintype "passive"))
      (node (ref "RP3") (pin "2") (pinfunction "2_2") (pintype "passive"))
    )
    (net (code "100") (name "Net-(QB3-G)") (class "Default")
      (node (ref "QB3") (pin "1") (pinfunction "G_1") (pintype "passive"))
      (node (ref "RBG3") (pin "1") (pinfunction "1_1") (pintype "passive"))
    )
    (net (code "101") (name "Net-(QB4-D)") (class "Default")
      (node (ref "QB4") (pin "3") (pinfunction "D_3") (pintype "passive"))
      (node (ref "RP4") (pin "2") (pinfunction "2_2") (pintype "passive"))
    )
    (net (code "102") (name "Net-(QB4-G)") (class "Default")
      (node (ref "QB4") (pin "1") (pinfunction "G_1") (pintype "passive"))
      (node (ref "RBG4") (pin "1") (pinfunction "1_1") (pintype "passive"))
    )
    (net (code "103") (name "Net-(QB5-D)") (class "Default")
      (node (ref "QB5") (pin "3") (pinfunction "D_3") (pintype "passive"))
      (node (ref "RP5") (pin "2") (pinfunction "2_2") (pintype "passive"))
    )
    (net (code "104") (name "Net-(QB5-G)") (class "Default")
      (node (ref "QB5") (pin "1") (pinfunction "G_1") (pintype "passive"))
      (node (ref "RBG5") (pin "1") (pinfunction "1_1") (pintype "passive"))
    )
    (net (code "105") (name "Net-(QB6-D)") (class "Default")
      (node (ref "QB6") (pin "3") (pinfunction "D_3") (pintype "passive"))
      (node (ref "RP6") (pin "2") (pinfunction "2_2") (pintype "passive"))
    )
    (net (code "106") (name "Net-(QB6-G)") (class "Default")
      (node (ref "QB6") (pin "1") (pinfunction "G_1") (pintype "passive"))
      (node (ref "RBG6") (pin "1") (pinfunction "1_1") (pintype "passive"))
    )
    (net (code "107") (name "Net-(QB7-D)") (class "Default")
      (node (ref "QB7") (pin "3") (pinfunction "D_3") (pintype "passive"))
      (node (ref "RP7") (pin "2") (pinfunction "2_2") (pintype "passive"))
    )
    (net (code "108") (name "Net-(QB7-G)") (class "Default")
      (node (ref "QB7") (pin "1") (pinfunction "G_1") (pintype "passive"))
      (node (ref "RBG7") (pin "1") (pinfunction "1_1") (pintype "passive"))
    )
    (net (code "109") (name "Net-(QB8-D)") (class "Default")
      (node (ref "QB8") (pin "3") (pinfunction "D_3") (pintype "passive"))
      (node (ref "RP8") (pin "2") (pinfunction "2_2") (pintype "passive"))
    )
    (net (code "110") (name "Net-(QB8-G)") (class "Default")
      (node (ref "QB8") (pin "1") (pinfunction "G_1") (pintype "passive"))
      (node (ref "RBG8") (pin "1") (pinfunction "1_1") (pintype "passive"))
    )
    (net (code "111") (name "Net-(QB9-D)") (class "Default")
      (node (ref "QB9") (pin "3") (pinfunction "D_3") (pintype "passive"))
      (node (ref "RP9") (pin "2") (pinfunction "2_2") (pintype "passive"))
    )
    (net (code "112") (name "Net-(QB9-G)") (class "Default")
      (node (ref "QB9") (pin "1") (pinfunction "G_1") (pintype "passive"))
      (node (ref "RBG9") (pin "1") (pinfunction "1_1") (pintype "passive"))
    )
    (net (code "113") (name "Net-(QB10-D)") (class "Default")
      (node (ref "QB10") (pin "3") (pinfunction "D_3") (pintype "passive"))
      (node (ref "RP10") (pin "2") (pinfunction "2_2") (pintype "passive"))
    )
    (net (code "114") (name "Net-(QB10-G)") (class "Default")
      (node (ref "QB10") (pin "1") (pinfunction "G_1") (pintype "passive"))
      (node (ref "RBG10") (pin "1") (pinfunction "1_1") (pintype "passive"))
    )
    (net (code "115") (name "Net-(QB11-D)") (class "Default")
      (node (ref "QB11") (pin "3") (pinfunction "D_3") (pintype "passive"))
      (node (ref "RP11") (pin "2") (pinfunction "2_2") (pintype "passive"))
    )
    (net (code "116") (name "Net-(QB11-G)") (class "Default")
      (node (ref "QB11") (pin "1") (pinfunction "G_1") (pintype "passive"))
      (node (ref "RBG11") (pin "1") (pinfunction "1_1") (pintype "passive"))
    )
    (net (code "117") (name "Net-(QB12-D)") (class "Default")
      (node (ref "QB12") (pin "3") (pinfunction "D_3") (pintype "passive"))
      (node (ref "RP12") (pin "2") (pinfunction "2_2") (pintype "passive"))
    )
    (net (code "118") (name "Net-(QB12-G)") (class "Default")
      (node (ref "QB12") (pin "1") (pinfunction "G_1") (pintype "passive"))
      (node (ref "RBG12") (pin "1") (pinfunction "1_1") (pintype "passive"))
    )
    (net (code "119") (name "SCK") (class "Default")
      (node (ref "IC2") (pin "41") (pinfunction "SCKI_41") (pintype "bidirectional"))
      (node (ref "R3") (pin "2") (pinfunction "2_2") (pintype "passive"))
      (node (ref "RCSB") (pin "1") (pinfunction "1_1") (pintype "passive"))
    )
    (net (code "120") (name "SDI") (class "Default")
      (node (ref "IC2") (pin "42") (pinfunction "SDI_42") (pintype "bidirectional"))
      (node (ref "R5") (pin "2") (pinfunction "2_2") (pintype "passive"))
      (node (ref "RCSB1") (pin "1") (pinfunction "1_1") (pintype "passive"))
    )
    (net (code "121") (name "SDO") (class "Default")
      (node (ref "IC2") (pin "43") (pinfunction "SDO_43") (pintype "bidirectional"))
      (node (ref "R4") (pin "2") (pinfunction "2_2") (pintype "passive"))
      (node (ref "RCSB2") (pin "1") (pinfunction "1_1") (pintype "passive"))
    )
    (net (code "122") (name "SWCLK") (class "Default")
      (node (ref "IC1") (pin "29") (pinfunction "PIO0_10/SWCLK/SCK0/CT16B0_MAT2_29") (pintype "bidirectional"))
      (node (ref "JP1") (pin "3") (pinfunction "3_3") (pintype "passive"))
    )
    (net (code "123") (name "V+") (class "Default")
      (node (ref "C1") (pin "+") (pinfunction "+_+") (pintype "passive"))
      (node (ref "CV") (pin "1") (pinfunction "1_1") (pintype "passive"))
      (node (ref "D1") (pin "C") (pinfunction "C_C") (pintype "passive"))
      (node (ref "IC2") (pin "1") (pinfunction "V+_1") (pintype "bidirectional"))
      (node (ref "Q1") (pin "3") (pinfunction "D_3") (pintype "passive"))
      (node (ref "RFSM1") (pin "2") (pinfunction "2_2") (pintype "passive"))
    )
    (net (code "124") (name "VREF") (class "Default")
      (node (ref "CVREF") (pin "2") (pinfunction "2_2") (pintype "passive"))
      (node (ref "IC2") (pin "31") (pinfunction "VREF_31") (pintype "bidirectional"))
    )
    (net (code "125") (name "VREG") (class "Default")
      (node (ref "CVREG") (pin "2") (pinfunction "2_2") (pintype "passive"))
      (node (ref "IC2") (pin "32") (pinfunction "VREG_32") (pintype "bidirectional"))
      (node (ref "R2") (pin "2") (pinfunction "2_2") (pintype "passive"))
      (node (ref "RCSB") (pin "2") (pinfunction "2_2") (pintype "passive"))
      (node (ref "RCSB1") (pin "2") (pinfunction "2_2") (pintype "passive"))
      (node (ref "RCSB2") (pin "2") (pinfunction "2_2") (pintype "passive"))
      (node (ref "RCSB3") (pin "2") (pinfunction "2_2") (pintype "passive"))
    )
    (net (code "126") (name "unconnected-(IC1-PIO0_2{slash}SSEL{slash}CT16B0_CAP0-Pad10)") (class "Default")
      (node (ref "IC1") (pin "10") (pinfunction "PIO0_2/SSEL/CT16B0_CAP0_10") (pintype "bidirectional"))
    )
    (net (code "127") (name "unconnected-(IC1-PIO0_4{slash}SCL-Pad15)") (class "Default")
      (node (ref "IC1") (pin "15") (pinfunction "PIO0_4/SCL_15") (pintype "bidirectional"))
    )
    (net (code "128") (name "unconnected-(IC1-PIO0_5{slash}SDA-Pad16)") (class "Default")
      (node (ref "IC1") (pin "16") (pinfunction "PIO0_5/SDA_16") (pintype "bidirectional"))
    )
    (net (code "129") (name "unconnected-(IC1-PIO0_6{slash}SCK0-Pad22)") (class "Default")
      (node (ref "IC1") (pin "22") (pinfunction "PIO0_6/SCK0_22") (pintype "bidirectional"))
    )
    (net (code "130") (name "unconnected-(IC1-PIO0_7{slash}~{CTS}-Pad23)") (class "Default")
      (node (ref "IC1") (pin "23") (pinfunction "PIO0_7/~{CTS}_23") (pintype "bidirectional"))
    )
    (net (code "131") (name "unconnected-(IC1-PIO0_8{slash}MISO0{slash}CT16B0_MAT0-Pad27)") (class "Default")
      (node (ref "IC1") (pin "27") (pinfunction "PIO0_8/MISO0/CT16B0_MAT0_27") (pintype "bidirectional"))
    )
    (net (code "132") (name "unconnected-(IC1-PIO1_5{slash}~{RTS}{slash}CT32B0_CAP0-Pad45)") (class "Default")
      (node (ref "IC1") (pin "45") (pinfunction "PIO1_5/~{RTS}/CT32B0_CAP0_45") (pintype "bidirectional"))
    )
    (net (code "133") (name "unconnected-(IC1-PIO1_6{slash}RXD{slash}CT32B0_MAT0-Pad46)") (class "Default")
      (node (ref "IC1") (pin "46") (pinfunction "PIO1_6/RXD/CT32B0_MAT0_46") (pintype "bidirectional"))
    )
    (net (code "134") (name "unconnected-(IC1-PIO1_7{slash}TXD{slash}CT32B0_MAT1-Pad47)") (class "Default")
      (node (ref "IC1") (pin "47") (pinfunction "PIO1_7/TXD/CT32B0_MAT1_47") (pintype "bidirectional"))
    )
    (net (code "135") (name "unconnected-(IC1-PIO1_8{slash}CT16B1_CAP0-Pad9)") (class "Default")
      (node (ref "IC1") (pin "9") (pinfunction "PIO1_8/CT16B1_CAP0_9") (pintype "bidirectional"))
    )
    (net (code "136") (name "unconnected-(IC1-PIO1_9{slash}CT16B1_MAT0-Pad17)") (class "Default")
      (node (ref "IC1") (pin "17") (pinfunction "PIO1_9/CT16B1_MAT0_17") (pintype "bidirectional"))
    )
    (net (code "137") (name "unconnected-(IC1-PIO2_4-Pad18)") (class "Default")
      (node (ref "IC1") (pin "18") (pinfunction "PIO2_4_18") (pintype "bidirectional"))
    )
    (net (code "138") (name "unconnected-(IC1-PIO2_5-Pad21)") (class "Default")
      (node (ref "IC1") (pin "21") (pinfunction "PIO2_5_21") (pintype "bidirectional"))
    )
    (net (code "139") (name "unconnected-(IC1-PIO2_7-Pad11)") (class "Default")
      (node (ref "IC1") (pin "11") (pinfunction "PIO2_7_11") (pintype "bidirectional"))
    )
    (net (code "140") (name "unconnected-(IC1-PIO2_8-Pad12)") (class "Default")
      (node (ref "IC1") (pin "12") (pinfunction "PIO2_8_12") (pintype "bidirectional"))
    )
    (net (code "141") (name "unconnected-(IC1-PIO2_9-Pad24)") (class "Default")
      (node (ref "IC1") (pin "24") (pinfunction "PIO2_9_24") (pintype "bidirectional"))
    )
    (net (code "142") (name "unconnected-(IC1-PIO2_10-Pad25)") (class "Default")
      (node (ref "IC1") (pin "25") (pinfunction "PIO2_10_25") (pintype "bidirectional"))
    )
    (net (code "143") (name "unconnected-(IC1-PIO2_11{slash}SCK0-Pad31)") (class "Default")
      (node (ref "IC1") (pin "31") (pinfunction "PIO2_11/SCK0_31") (pintype "bidirectional"))
    )
    (net (code "144") (name "unconnected-(IC1-PIO3_0{slash}~{DTR}-Pad36)") (class "Default")
      (node (ref "IC1") (pin "36") (pinfunction "PIO3_0/~{DTR}_36") (pintype "bidirectional"))
    )
    (net (code "145") (name "unconnected-(IC1-PIO3_1{slash}~{DSR}-Pad37)") (class "Default")
      (node (ref "IC1") (pin "37") (pinfunction "PIO3_1/~{DSR}_37") (pintype "bidirectional"))
    )
    (net (code "146") (name "unconnected-(IC1-PIO3_2{slash}~{DCD}-Pad43)") (class "Default")
      (node (ref "IC1") (pin "43") (pinfunction "PIO3_2/~{DCD}_43") (pintype "bidirectional"))
    )
    (net (code "147") (name "unconnected-(IC4-VRF-Pad5)") (class "Default")
      (node (ref "IC4") (pin "5") (pinfunction "VRF_5") (pintype "bidirectional"))
    )
    (net (code "148") (name "~{RESET}") (class "Default")
      (node (ref "C17") (pin "1") (pinfunction "1_1") (pintype "passive"))
      (node (ref "C24") (pin "1") (pinfunction "1_1") (pintype "passive"))
      (node (ref "IC1") (pin "3") (pinfunction "PIO0_0/~{RESET}_3") (pintype "bidirectional"))
      (node (ref "JP1") (pin "2") (pinfunction "2_2") (pintype "passive"))
      (node (ref "R9") (pin "2") (pinfunction "2_2") (pintype "passive"))
    )
  )
)
